# SCCB1508-00.net
KiCad netlist of a schematic drawn in EAGLE
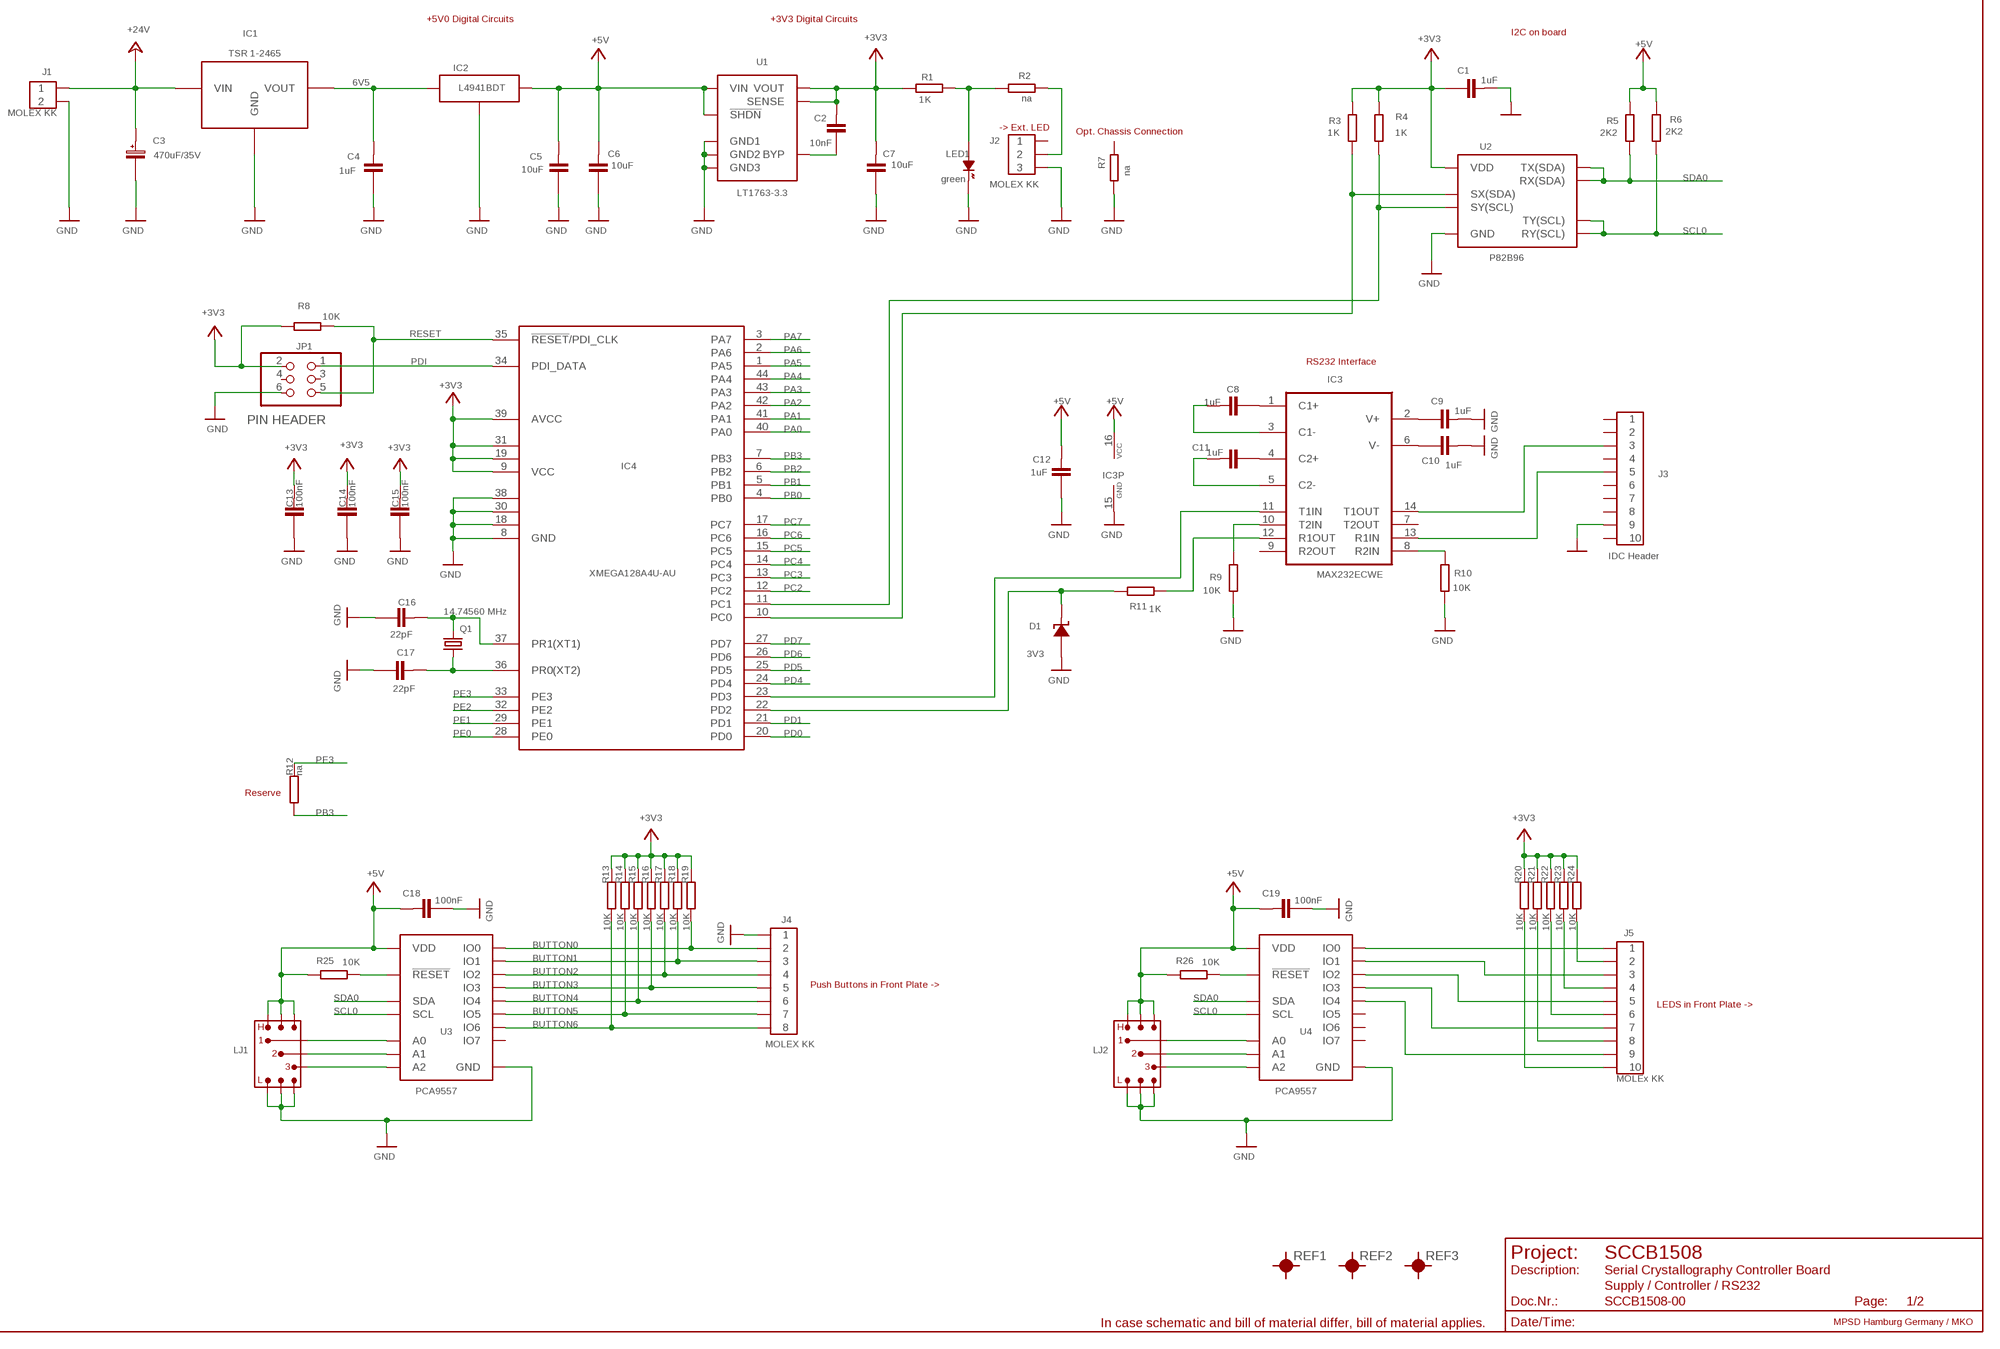
[diagram p0: schematic, sheet 1]
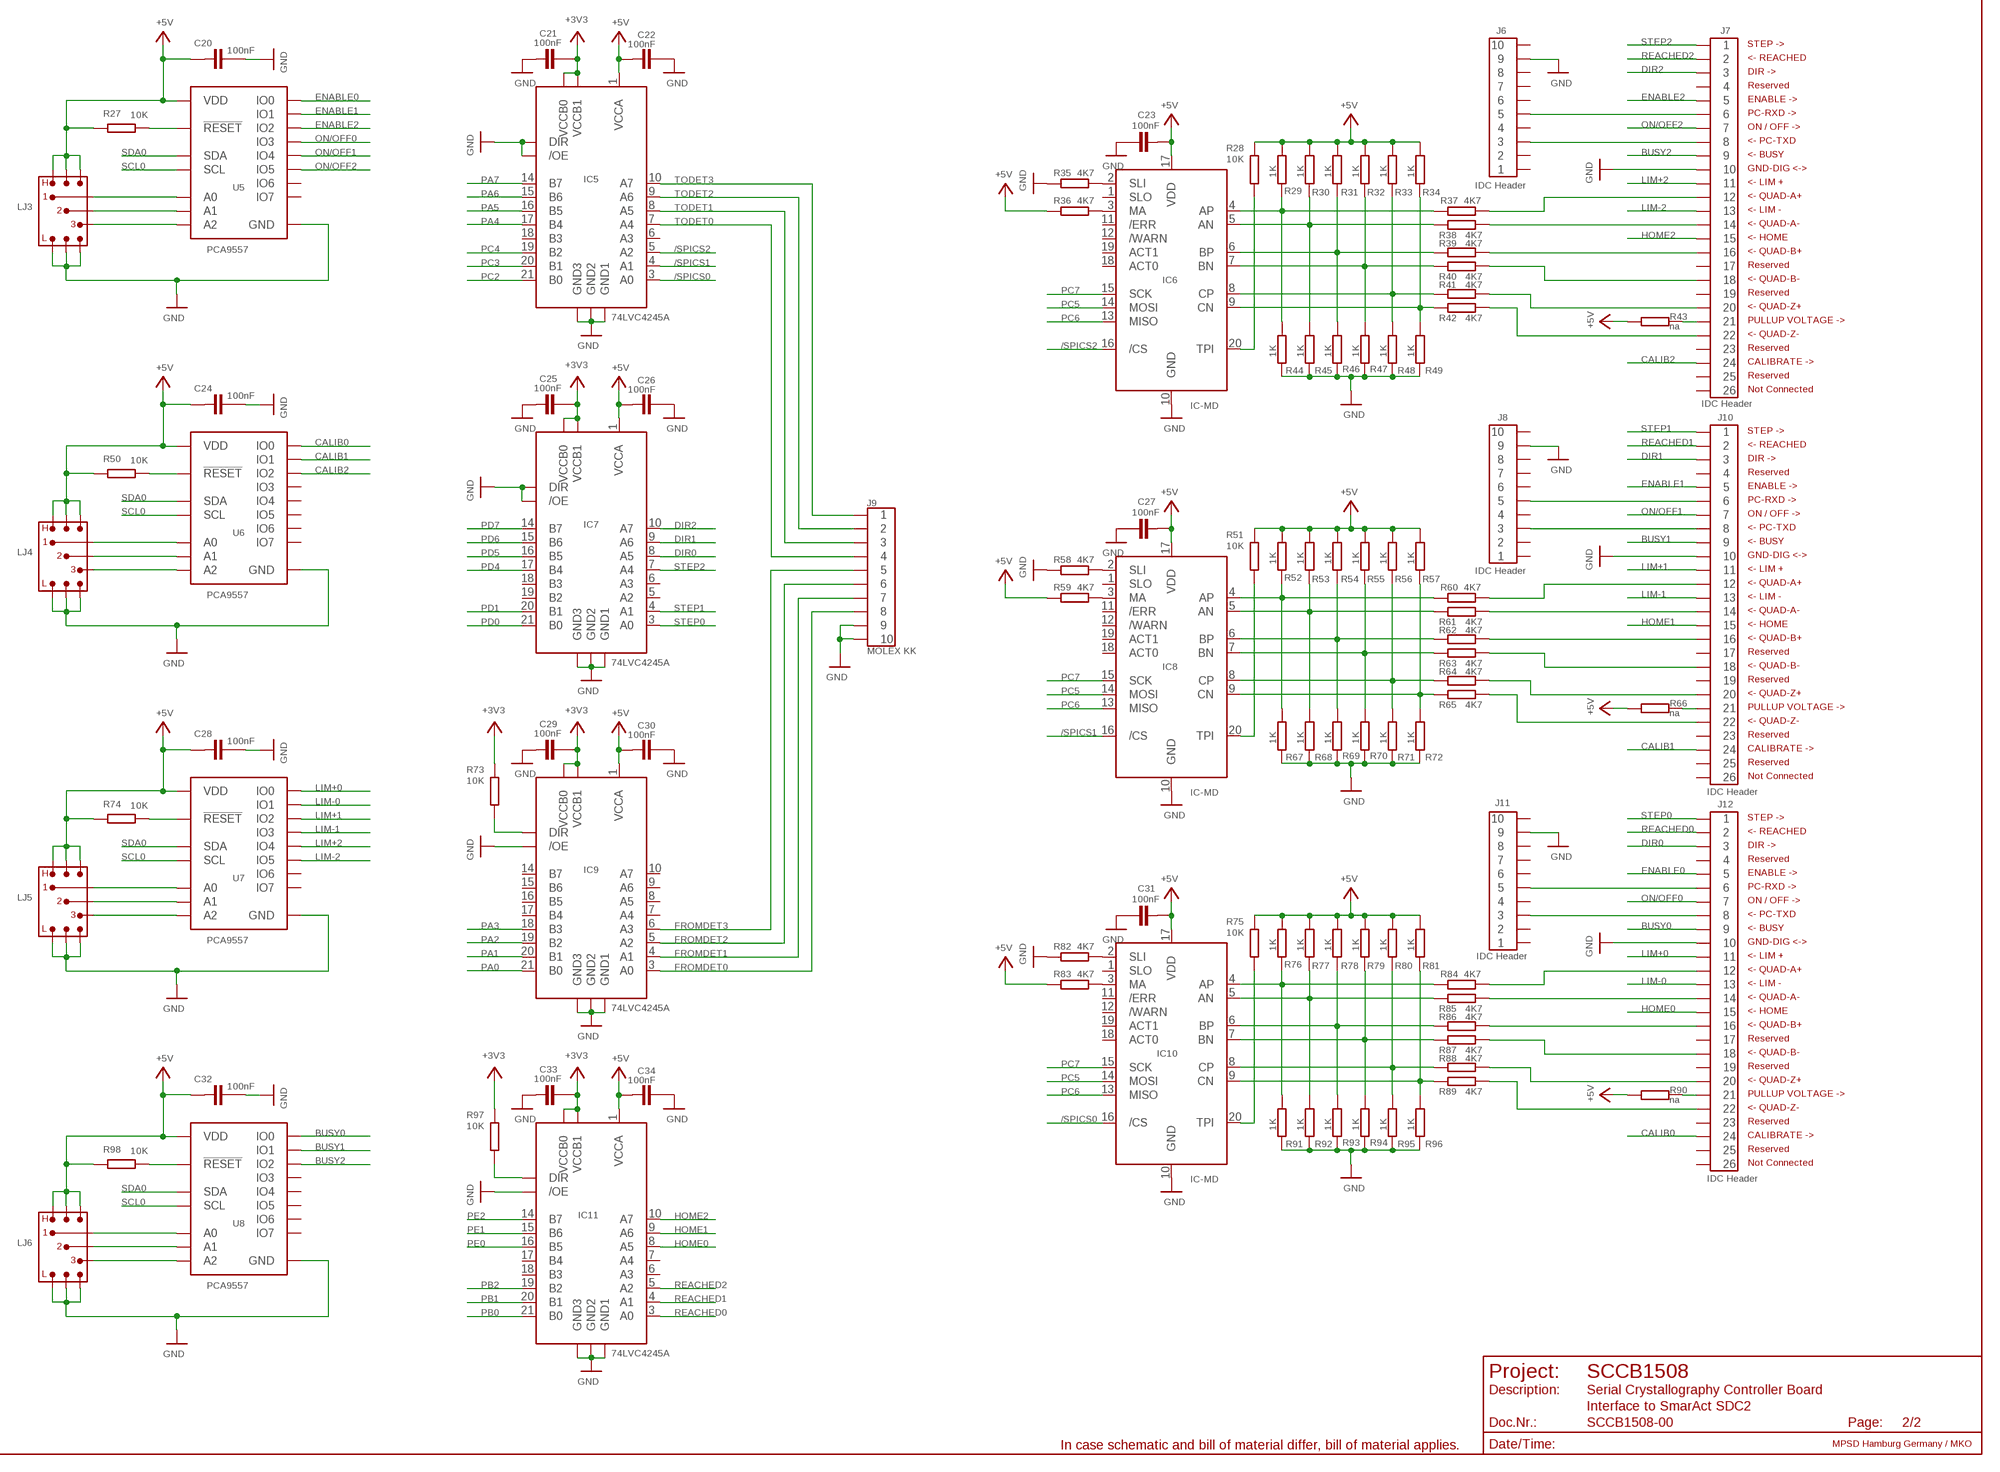
[diagram p1: schematic, sheet 2]

(export (version "E")
  (design (tool "Eeschema 10.0.6"))
  (components
    (comp (ref "C1")
      (value "1uF")
      (footprint "eagle-import:0805")
      (libsource (lib "eagle-import") (part "C_0805"))
    )
    (comp (ref "C2")
      (value "10nF")
      (footprint "eagle-import:0603")
      (libsource (lib "eagle-import") (part "C_0603"))
    )
    (comp (ref "C3")
      (value "470uF/35V")
      (footprint "eagle-import:C_POL_RM5_D16")
      (libsource (lib "eagle-import") (part "C_POL_RM5_D16"))
    )
    (comp (ref "C4")
      (value "1uF")
      (footprint "eagle-import:0805")
      (libsource (lib "eagle-import") (part "C_0805"))
    )
    (comp (ref "C5")
      (value "10uF")
      (footprint "eagle-import:1206")
      (libsource (lib "eagle-import") (part "C_1206"))
    )
    (comp (ref "C6")
      (value "10uF")
      (footprint "eagle-import:1206")
      (libsource (lib "eagle-import") (part "C_1206"))
    )
    (comp (ref "C7")
      (value "10uF")
      (footprint "eagle-import:1206")
      (libsource (lib "eagle-import") (part "C_1206"))
    )
    (comp (ref "C8")
      (value "1uF")
      (footprint "eagle-import:0805")
      (libsource (lib "eagle-import") (part "C_0805"))
    )
    (comp (ref "C9")
      (value "1uF")
      (footprint "eagle-import:0805")
      (libsource (lib "eagle-import") (part "C_0805"))
    )
    (comp (ref "C10")
      (value "1uF")
      (footprint "eagle-import:0805")
      (libsource (lib "eagle-import") (part "C_0805"))
    )
    (comp (ref "C11")
      (value "1uF")
      (footprint "eagle-import:0805")
      (libsource (lib "eagle-import") (part "C_0805"))
    )
    (comp (ref "C12")
      (value "1uF")
      (footprint "eagle-import:0805")
      (libsource (lib "eagle-import") (part "C_0805"))
    )
    (comp (ref "C13")
      (value "100nF")
      (footprint "eagle-import:0603")
      (libsource (lib "eagle-import") (part "C_0603"))
    )
    (comp (ref "C14")
      (value "100nF")
      (footprint "eagle-import:0603")
      (libsource (lib "eagle-import") (part "C_0603"))
    )
    (comp (ref "C15")
      (value "100nF")
      (footprint "eagle-import:0603")
      (libsource (lib "eagle-import") (part "C_0603"))
    )
    (comp (ref "C16")
      (value "22pF")
      (footprint "eagle-import:0603")
      (libsource (lib "eagle-import") (part "C_0603"))
    )
    (comp (ref "C17")
      (value "22pF")
      (footprint "eagle-import:0603")
      (libsource (lib "eagle-import") (part "C_0603"))
    )
    (comp (ref "C18")
      (value "100nF")
      (footprint "eagle-import:0603")
      (libsource (lib "eagle-import") (part "C_0603"))
    )
    (comp (ref "C19")
      (value "100nF")
      (footprint "eagle-import:0603")
      (libsource (lib "eagle-import") (part "C_0603"))
    )
    (comp (ref "D1")
      (value "3V3")
      (footprint "eagle-import:SOT_23")
      (libsource (lib "eagle-import") (part "D_ZENER_SOT23"))
    )
    (comp (ref "IC1")
      (value "TSR 1-2465")
      (footprint "eagle-import:TRACO_TSR_1")
      (libsource (lib "eagle-import") (part "TRACO_TSR_1"))
    )
    (comp (ref "IC2")
      (value "L4941BDT")
      (footprint "eagle-import:D_PAK")
      (libsource (lib "eagle-import") (part "VOLTREG_LIN_3POL_D-PAK"))
    )
    (comp (ref "IC3")
      (value "MAX232ECWE")
      (footprint "eagle-import:SO16L")
      (fields (field (name "MF") "MAXIM") (field (name "MPN") "MAX232ECWE+"))
      (libsource (lib "eagle-import") (part "MAX232ECWE"))
    )
    (comp (ref "IC4")
      (value "XMEGA128A4U-AU")
      (footprint "eagle-import:TQFP44")
      (libsource (lib "eagle-import") (part "XMEGA16A4A"))
    )
    (comp (ref "J1")
      (value "MOLEX KK")
      (footprint "eagle-import:MOLEX_KK_02POL")
      (libsource (lib "eagle-import") (part "CON_02_MOLEX_KK"))
    )
    (comp (ref "J2")
      (value "MOLEX KK")
      (footprint "eagle-import:MOLEX_KK_03POL")
      (libsource (lib "eagle-import") (part "CON_03_MOLEX_KK"))
    )
    (comp (ref "J3")
      (value "IDC Header")
      (footprint "eagle-import:IDC_WANNE_10POL")
      (libsource (lib "eagle-import") (part "CON_10_IDC_10"))
    )
    (comp (ref "J4")
      (value "MOLEX KK")
      (footprint "eagle-import:MOLEX_KK_08POL")
      (libsource (lib "eagle-import") (part "CON_08_MOLEX_KK"))
    )
    (comp (ref "J5")
      (value "MOLEx KK")
      (footprint "eagle-import:MOLEX_KK_10POL")
      (libsource (lib "eagle-import") (part "CON_10_MOLEX-KK"))
    )
    (comp (ref "JP1")
      (value "PIN HEADER")
      (footprint "eagle-import:2X03")
      (libsource (lib "eagle-import") (part "PINHD-2X3"))
    )
    (comp (ref "LED1")
      (value "green")
      (footprint "eagle-import:0603_POL")
      (libsource (lib "eagle-import") (part "D_LED_0603"))
    )
    (comp (ref "LJ1")
      (value "LOETJUMPER_3KHL_")
      (footprint "eagle-import:LOETJUMPER_3KHL")
      (libsource (lib "eagle-import") (part "LOETJUMPER_3KHL_"))
    )
    (comp (ref "LJ2")
      (value "LOETJUMPER_3KHL_")
      (footprint "eagle-import:LOETJUMPER_3KHL")
      (libsource (lib "eagle-import") (part "LOETJUMPER_3KHL_"))
    )
    (comp (ref "Q1")
      (value "14.74560 MHz")
      (footprint "eagle-import:HC49UP")
      (libsource (lib "eagle-import") (part "CRYSTALHC49UP"))
    )
    (comp (ref "R1")
      (value "1K")
      (footprint "eagle-import:0603")
      (libsource (lib "eagle-import") (part "R_0603"))
    )
    (comp (ref "R2")
      (value "na")
      (footprint "eagle-import:1206")
      (libsource (lib "eagle-import") (part "R_1206"))
    )
    (comp (ref "R3")
      (value "1K")
      (footprint "eagle-import:0603")
      (libsource (lib "eagle-import") (part "R_0603"))
    )
    (comp (ref "R4")
      (value "1K")
      (footprint "eagle-import:0603")
      (libsource (lib "eagle-import") (part "R_0603"))
    )
    (comp (ref "R5")
      (value "2K2")
      (footprint "eagle-import:0603")
      (libsource (lib "eagle-import") (part "R_0603"))
    )
    (comp (ref "R6")
      (value "2K2")
      (footprint "eagle-import:0603")
      (libsource (lib "eagle-import") (part "R_0603"))
    )
    (comp (ref "R7")
      (value "na")
      (footprint "eagle-import:0603")
      (libsource (lib "eagle-import") (part "R_0603"))
    )
    (comp (ref "R8")
      (value "10K")
      (footprint "eagle-import:0603")
      (libsource (lib "eagle-import") (part "R_0603"))
    )
    (comp (ref "R9")
      (value "10K")
      (footprint "eagle-import:0603")
      (libsource (lib "eagle-import") (part "R_0603"))
    )
    (comp (ref "R10")
      (value "10K")
      (footprint "eagle-import:0603")
      (libsource (lib "eagle-import") (part "R_0603"))
    )
    (comp (ref "R11")
      (value "1K")
      (footprint "eagle-import:0603")
      (libsource (lib "eagle-import") (part "R_0603"))
    )
    (comp (ref "R12")
      (value "na")
      (footprint "eagle-import:0805")
      (libsource (lib "eagle-import") (part "R_0805"))
    )
    (comp (ref "R13")
      (value "10K")
      (footprint "eagle-import:0603")
      (libsource (lib "eagle-import") (part "R_0603"))
    )
    (comp (ref "R14")
      (value "10K")
      (footprint "eagle-import:0603")
      (libsource (lib "eagle-import") (part "R_0603"))
    )
    (comp (ref "R15")
      (value "10K")
      (footprint "eagle-import:0603")
      (libsource (lib "eagle-import") (part "R_0603"))
    )
    (comp (ref "R16")
      (value "10K")
      (footprint "eagle-import:0603")
      (libsource (lib "eagle-import") (part "R_0603"))
    )
    (comp (ref "R17")
      (value "10K")
      (footprint "eagle-import:0603")
      (libsource (lib "eagle-import") (part "R_0603"))
    )
    (comp (ref "R18")
      (value "10K")
      (footprint "eagle-import:0603")
      (libsource (lib "eagle-import") (part "R_0603"))
    )
    (comp (ref "R19")
      (value "10K")
      (footprint "eagle-import:0603")
      (libsource (lib "eagle-import") (part "R_0603"))
    )
    (comp (ref "R20")
      (value "10K")
      (footprint "eagle-import:0603")
      (libsource (lib "eagle-import") (part "R_0603"))
    )
    (comp (ref "R21")
      (value "10K")
      (footprint "eagle-import:0603")
      (libsource (lib "eagle-import") (part "R_0603"))
    )
    (comp (ref "R22")
      (value "10K")
      (footprint "eagle-import:0603")
      (libsource (lib "eagle-import") (part "R_0603"))
    )
    (comp (ref "R23")
      (value "10K")
      (footprint "eagle-import:0603")
      (libsource (lib "eagle-import") (part "R_0603"))
    )
    (comp (ref "R24")
      (value "10K")
      (footprint "eagle-import:0603")
      (libsource (lib "eagle-import") (part "R_0603"))
    )
    (comp (ref "R25")
      (value "10K")
      (footprint "eagle-import:0603")
      (libsource (lib "eagle-import") (part "R_0603"))
    )
    (comp (ref "R26")
      (value "10K")
      (footprint "eagle-import:0603")
      (libsource (lib "eagle-import") (part "R_0603"))
    )
    (comp (ref "REF1")
      (value "PASSERMARKE_1.0")
      (footprint "eagle-import:PASSERMARKE_01")
      (libsource (lib "eagle-import") (part "PASSERMARKE_1.0"))
    )
    (comp (ref "REF2")
      (value "PASSERMARKE_1.0")
      (footprint "eagle-import:PASSERMARKE_01")
      (libsource (lib "eagle-import") (part "PASSERMARKE_1.0"))
    )
    (comp (ref "REF3")
      (value "PASSERMARKE_1.0")
      (footprint "eagle-import:PASSERMARKE_01")
      (libsource (lib "eagle-import") (part "PASSERMARKE_1.0"))
    )
    (comp (ref "U1")
      (value "LT1763-3.3")
      (footprint "eagle-import:SOIC127P-6-8POL")
      (libsource (lib "eagle-import") (part "LT1763_SO8_ZE"))
    )
    (comp (ref "U2")
      (value "P82B96")
      (footprint "eagle-import:SO_8_BW3.9MM")
      (libsource (lib "eagle-import") (part "P82B96_SO8"))
    )
    (comp (ref "U3")
      (value "PCA9557")
      (footprint "eagle-import:SO_16_BW3.9MM")
      (libsource (lib "eagle-import") (part "PCA9557_SO_16"))
    )
    (comp (ref "U4")
      (value "PCA9557")
      (footprint "eagle-import:SO_16_BW3.9MM")
      (libsource (lib "eagle-import") (part "PCA9557_SO_16"))
    )
    (comp (ref "C20")
      (value "100nF")
      (footprint "eagle-import:0603")
      (libsource (lib "eagle-import") (part "C_0603"))
    )
    (comp (ref "C21")
      (value "100nF")
      (footprint "eagle-import:0603")
      (libsource (lib "eagle-import") (part "C_0603"))
    )
    (comp (ref "C22")
      (value "100nF")
      (footprint "eagle-import:0603")
      (libsource (lib "eagle-import") (part "C_0603"))
    )
    (comp (ref "C23")
      (value "100nF")
      (footprint "eagle-import:0603")
      (libsource (lib "eagle-import") (part "C_0603"))
    )
    (comp (ref "C24")
      (value "100nF")
      (footprint "eagle-import:0603")
      (libsource (lib "eagle-import") (part "C_0603"))
    )
    (comp (ref "C25")
      (value "100nF")
      (footprint "eagle-import:0603")
      (libsource (lib "eagle-import") (part "C_0603"))
    )
    (comp (ref "C26")
      (value "100nF")
      (footprint "eagle-import:0603")
      (libsource (lib "eagle-import") (part "C_0603"))
    )
    (comp (ref "C27")
      (value "100nF")
      (footprint "eagle-import:0603")
      (libsource (lib "eagle-import") (part "C_0603"))
    )
    (comp (ref "C28")
      (value "100nF")
      (footprint "eagle-import:0603")
      (libsource (lib "eagle-import") (part "C_0603"))
    )
    (comp (ref "C29")
      (value "100nF")
      (footprint "eagle-import:0603")
      (libsource (lib "eagle-import") (part "C_0603"))
    )
    (comp (ref "C30")
      (value "100nF")
      (footprint "eagle-import:0603")
      (libsource (lib "eagle-import") (part "C_0603"))
    )
    (comp (ref "C31")
      (value "100nF")
      (footprint "eagle-import:0603")
      (libsource (lib "eagle-import") (part "C_0603"))
    )
    (comp (ref "C32")
      (value "100nF")
      (footprint "eagle-import:0603")
      (libsource (lib "eagle-import") (part "C_0603"))
    )
    (comp (ref "C33")
      (value "100nF")
      (footprint "eagle-import:0603")
      (libsource (lib "eagle-import") (part "C_0603"))
    )
    (comp (ref "C34")
      (value "100nF")
      (footprint "eagle-import:0603")
      (libsource (lib "eagle-import") (part "C_0603"))
    )
    (comp (ref "IC5")
      (value "74LVC4245A")
      (footprint "eagle-import:SO_24_BW5.3MM")
      (libsource (lib "eagle-import") (part "74LVC4245A_SSOP24"))
    )
    (comp (ref "IC6")
      (value "IC-MD")
      (footprint "eagle-import:SSOP_20_BW4.4")
      (libsource (lib "eagle-import") (part "IC-MD_SSOP-20"))
    )
    (comp (ref "IC7")
      (value "74LVC4245A")
      (footprint "eagle-import:SO_24_BW5.3MM")
      (libsource (lib "eagle-import") (part "74LVC4245A_SSOP24"))
    )
    (comp (ref "IC8")
      (value "IC-MD")
      (footprint "eagle-import:SSOP_20_BW4.4")
      (libsource (lib "eagle-import") (part "IC-MD_SSOP-20"))
    )
    (comp (ref "IC9")
      (value "74LVC4245A")
      (footprint "eagle-import:SO_24_BW5.3MM")
      (libsource (lib "eagle-import") (part "74LVC4245A_SSOP24"))
    )
    (comp (ref "IC10")
      (value "IC-MD")
      (footprint "eagle-import:SSOP_20_BW4.4")
      (libsource (lib "eagle-import") (part "IC-MD_SSOP-20"))
    )
    (comp (ref "IC11")
      (value "74LVC4245A")
      (footprint "eagle-import:SO_24_BW5.3MM")
      (libsource (lib "eagle-import") (part "74LVC4245A_SSOP24"))
    )
    (comp (ref "J6")
      (value "IDC Header")
      (footprint "eagle-import:IDC_WANNE_10POL")
      (libsource (lib "eagle-import") (part "CON_10_IDC_10"))
    )
    (comp (ref "J7")
      (value "IDC Header")
      (footprint "eagle-import:IDC_WANNE_26POL")
      (libsource (lib "eagle-import") (part "CON_26_IDC_HEADER"))
    )
    (comp (ref "J8")
      (value "IDC Header")
      (footprint "eagle-import:IDC_WANNE_10POL")
      (libsource (lib "eagle-import") (part "CON_10_IDC_10"))
    )
    (comp (ref "J9")
      (value "MOLEX KK")
      (footprint "eagle-import:MOLEX_KK_10POL")
      (libsource (lib "eagle-import") (part "CON_10_MOLEX-KK"))
    )
    (comp (ref "J10")
      (value "IDC Header")
      (footprint "eagle-import:IDC_WANNE_26POL")
      (libsource (lib "eagle-import") (part "CON_26_IDC_HEADER"))
    )
    (comp (ref "J11")
      (value "IDC Header")
      (footprint "eagle-import:IDC_WANNE_10POL")
      (libsource (lib "eagle-import") (part "CON_10_IDC_10"))
    )
    (comp (ref "J12")
      (value "IDC Header")
      (footprint "eagle-import:IDC_WANNE_26POL")
      (libsource (lib "eagle-import") (part "CON_26_IDC_HEADER"))
    )
    (comp (ref "LJ3")
      (value "LOETJUMPER_3KHL_")
      (footprint "eagle-import:LOETJUMPER_3KHL")
      (libsource (lib "eagle-import") (part "LOETJUMPER_3KHL_"))
    )
    (comp (ref "LJ4")
      (value "LOETJUMPER_3KHL_")
      (footprint "eagle-import:LOETJUMPER_3KHL")
      (libsource (lib "eagle-import") (part "LOETJUMPER_3KHL_"))
    )
    (comp (ref "LJ5")
      (value "LOETJUMPER_3KHL_")
      (footprint "eagle-import:LOETJUMPER_3KHL")
      (libsource (lib "eagle-import") (part "LOETJUMPER_3KHL_"))
    )
    (comp (ref "LJ6")
      (value "LOETJUMPER_3KHL_")
      (footprint "eagle-import:LOETJUMPER_3KHL")
      (libsource (lib "eagle-import") (part "LOETJUMPER_3KHL_"))
    )
    (comp (ref "R27")
      (value "10K")
      (footprint "eagle-import:0603")
      (libsource (lib "eagle-import") (part "R_0603"))
    )
    (comp (ref "R28")
      (value "10K")
      (footprint "eagle-import:0603")
      (libsource (lib "eagle-import") (part "R_0603"))
    )
    (comp (ref "R29")
      (value "1K")
      (footprint "eagle-import:0603")
      (libsource (lib "eagle-import") (part "R_0603"))
    )
    (comp (ref "R30")
      (value "1K")
      (footprint "eagle-import:0603")
      (libsource (lib "eagle-import") (part "R_0603"))
    )
    (comp (ref "R31")
      (value "1K")
      (footprint "eagle-import:0603")
      (libsource (lib "eagle-import") (part "R_0603"))
    )
    (comp (ref "R32")
      (value "1K")
      (footprint "eagle-import:0603")
      (libsource (lib "eagle-import") (part "R_0603"))
    )
    (comp (ref "R33")
      (value "1K")
      (footprint "eagle-import:0603")
      (libsource (lib "eagle-import") (part "R_0603"))
    )
    (comp (ref "R34")
      (value "1K")
      (footprint "eagle-import:0603")
      (libsource (lib "eagle-import") (part "R_0603"))
    )
    (comp (ref "R35")
      (value "4K7")
      (footprint "eagle-import:0603")
      (libsource (lib "eagle-import") (part "R_0603"))
    )
    (comp (ref "R36")
      (value "4K7")
      (footprint "eagle-import:0603")
      (libsource (lib "eagle-import") (part "R_0603"))
    )
    (comp (ref "R37")
      (value "4K7")
      (footprint "eagle-import:0603")
      (libsource (lib "eagle-import") (part "R_0603"))
    )
    (comp (ref "R38")
      (value "4K7")
      (footprint "eagle-import:0603")
      (libsource (lib "eagle-import") (part "R_0603"))
    )
    (comp (ref "R39")
      (value "4K7")
      (footprint "eagle-import:0603")
      (libsource (lib "eagle-import") (part "R_0603"))
    )
    (comp (ref "R40")
      (value "4K7")
      (footprint "eagle-import:0603")
      (libsource (lib "eagle-import") (part "R_0603"))
    )
    (comp (ref "R41")
      (value "4K7")
      (footprint "eagle-import:0603")
      (libsource (lib "eagle-import") (part "R_0603"))
    )
    (comp (ref "R42")
      (value "4K7")
      (footprint "eagle-import:0603")
      (libsource (lib "eagle-import") (part "R_0603"))
    )
    (comp (ref "R43")
      (value "na")
      (footprint "eagle-import:RM10L10B2.5")
      (libsource (lib "eagle-import") (part "R_RM10B2.5"))
    )
    (comp (ref "R44")
      (value "1K")
      (footprint "eagle-import:0603")
      (libsource (lib "eagle-import") (part "R_0603"))
    )
    (comp (ref "R45")
      (value "1K")
      (footprint "eagle-import:0603")
      (libsource (lib "eagle-import") (part "R_0603"))
    )
    (comp (ref "R46")
      (value "1K")
      (footprint "eagle-import:0603")
      (libsource (lib "eagle-import") (part "R_0603"))
    )
    (comp (ref "R47")
      (value "1K")
      (footprint "eagle-import:0603")
      (libsource (lib "eagle-import") (part "R_0603"))
    )
    (comp (ref "R48")
      (value "1K")
      (footprint "eagle-import:0603")
      (libsource (lib "eagle-import") (part "R_0603"))
    )
    (comp (ref "R49")
      (value "1K")
      (footprint "eagle-import:0603")
      (libsource (lib "eagle-import") (part "R_0603"))
    )
    (comp (ref "R50")
      (value "10K")
      (footprint "eagle-import:0603")
      (libsource (lib "eagle-import") (part "R_0603"))
    )
    (comp (ref "R51")
      (value "10K")
      (footprint "eagle-import:0603")
      (libsource (lib "eagle-import") (part "R_0603"))
    )
    (comp (ref "R52")
      (value "1K")
      (footprint "eagle-import:0603")
      (libsource (lib "eagle-import") (part "R_0603"))
    )
    (comp (ref "R53")
      (value "1K")
      (footprint "eagle-import:0603")
      (libsource (lib "eagle-import") (part "R_0603"))
    )
    (comp (ref "R54")
      (value "1K")
      (footprint "eagle-import:0603")
      (libsource (lib "eagle-import") (part "R_0603"))
    )
    (comp (ref "R55")
      (value "1K")
      (footprint "eagle-import:0603")
      (libsource (lib "eagle-import") (part "R_0603"))
    )
    (comp (ref "R56")
      (value "1K")
      (footprint "eagle-import:0603")
      (libsource (lib "eagle-import") (part "R_0603"))
    )
    (comp (ref "R57")
      (value "1K")
      (footprint "eagle-import:0603")
      (libsource (lib "eagle-import") (part "R_0603"))
    )
    (comp (ref "R58")
      (value "4K7")
      (footprint "eagle-import:0603")
      (libsource (lib "eagle-import") (part "R_0603"))
    )
    (comp (ref "R59")
      (value "4K7")
      (footprint "eagle-import:0603")
      (libsource (lib "eagle-import") (part "R_0603"))
    )
    (comp (ref "R60")
      (value "4K7")
      (footprint "eagle-import:0603")
      (libsource (lib "eagle-import") (part "R_0603"))
    )
    (comp (ref "R61")
      (value "4K7")
      (footprint "eagle-import:0603")
      (libsource (lib "eagle-import") (part "R_0603"))
    )
    (comp (ref "R62")
      (value "4K7")
      (footprint "eagle-import:0603")
      (libsource (lib "eagle-import") (part "R_0603"))
    )
    (comp (ref "R63")
      (value "4K7")
      (footprint "eagle-import:0603")
      (libsource (lib "eagle-import") (part "R_0603"))
    )
    (comp (ref "R64")
      (value "4K7")
      (footprint "eagle-import:0603")
      (libsource (lib "eagle-import") (part "R_0603"))
    )
    (comp (ref "R65")
      (value "4K7")
      (footprint "eagle-import:0603")
      (libsource (lib "eagle-import") (part "R_0603"))
    )
    (comp (ref "R66")
      (value "na")
      (footprint "eagle-import:RM10L10B2.5")
      (libsource (lib "eagle-import") (part "R_RM10B2.5"))
    )
    (comp (ref "R67")
      (value "1K")
      (footprint "eagle-import:0603")
      (libsource (lib "eagle-import") (part "R_0603"))
    )
    (comp (ref "R68")
      (value "1K")
      (footprint "eagle-import:0603")
      (libsource (lib "eagle-import") (part "R_0603"))
    )
    (comp (ref "R69")
      (value "1K")
      (footprint "eagle-import:0603")
      (libsource (lib "eagle-import") (part "R_0603"))
    )
    (comp (ref "R70")
      (value "1K")
      (footprint "eagle-import:0603")
      (libsource (lib "eagle-import") (part "R_0603"))
    )
    (comp (ref "R71")
      (value "1K")
      (footprint "eagle-import:0603")
      (libsource (lib "eagle-import") (part "R_0603"))
    )
    (comp (ref "R72")
      (value "1K")
      (footprint "eagle-import:0603")
      (libsource (lib "eagle-import") (part "R_0603"))
    )
    (comp (ref "R73")
      (value "10K")
      (footprint "eagle-import:0603")
      (libsource (lib "eagle-import") (part "R_0603"))
    )
    (comp (ref "R74")
      (value "10K")
      (footprint "eagle-import:0603")
      (libsource (lib "eagle-import") (part "R_0603"))
    )
    (comp (ref "R75")
      (value "10K")
      (footprint "eagle-import:0603")
      (libsource (lib "eagle-import") (part "R_0603"))
    )
    (comp (ref "R76")
      (value "1K")
      (footprint "eagle-import:0603")
      (libsource (lib "eagle-import") (part "R_0603"))
    )
    (comp (ref "R77")
      (value "1K")
      (footprint "eagle-import:0603")
      (libsource (lib "eagle-import") (part "R_0603"))
    )
    (comp (ref "R78")
      (value "1K")
      (footprint "eagle-import:0603")
      (libsource (lib "eagle-import") (part "R_0603"))
    )
    (comp (ref "R79")
      (value "1K")
      (footprint "eagle-import:0603")
      (libsource (lib "eagle-import") (part "R_0603"))
    )
    (comp (ref "R80")
      (value "1K")
      (footprint "eagle-import:0603")
      (libsource (lib "eagle-import") (part "R_0603"))
    )
    (comp (ref "R81")
      (value "1K")
      (footprint "eagle-import:0603")
      (libsource (lib "eagle-import") (part "R_0603"))
    )
    (comp (ref "R82")
      (value "4K7")
      (footprint "eagle-import:0603")
      (libsource (lib "eagle-import") (part "R_0603"))
    )
    (comp (ref "R83")
      (value "4K7")
      (footprint "eagle-import:0603")
      (libsource (lib "eagle-import") (part "R_0603"))
    )
    (comp (ref "R84")
      (value "4K7")
      (footprint "eagle-import:0603")
      (libsource (lib "eagle-import") (part "R_0603"))
    )
    (comp (ref "R85")
      (value "4K7")
      (footprint "eagle-import:0603")
      (libsource (lib "eagle-import") (part "R_0603"))
    )
    (comp (ref "R86")
      (value "4K7")
      (footprint "eagle-import:0603")
      (libsource (lib "eagle-import") (part "R_0603"))
    )
    (comp (ref "R87")
      (value "4K7")
      (footprint "eagle-import:0603")
      (libsource (lib "eagle-import") (part "R_0603"))
    )
    (comp (ref "R88")
      (value "4K7")
      (footprint "eagle-import:0603")
      (libsource (lib "eagle-import") (part "R_0603"))
    )
    (comp (ref "R89")
      (value "4K7")
      (footprint "eagle-import:0603")
      (libsource (lib "eagle-import") (part "R_0603"))
    )
    (comp (ref "R90")
      (value "na")
      (footprint "eagle-import:RM10L10B2.5")
      (libsource (lib "eagle-import") (part "R_RM10B2.5"))
    )
    (comp (ref "R91")
      (value "1K")
      (footprint "eagle-import:0603")
      (libsource (lib "eagle-import") (part "R_0603"))
    )
    (comp (ref "R92")
      (value "1K")
      (footprint "eagle-import:0603")
      (libsource (lib "eagle-import") (part "R_0603"))
    )
    (comp (ref "R93")
      (value "1K")
      (footprint "eagle-import:0603")
      (libsource (lib "eagle-import") (part "R_0603"))
    )
    (comp (ref "R94")
      (value "1K")
      (footprint "eagle-import:0603")
      (libsource (lib "eagle-import") (part "R_0603"))
    )
    (comp (ref "R95")
      (value "1K")
      (footprint "eagle-import:0603")
      (libsource (lib "eagle-import") (part "R_0603"))
    )
    (comp (ref "R96")
      (value "1K")
      (footprint "eagle-import:0603")
      (libsource (lib "eagle-import") (part "R_0603"))
    )
    (comp (ref "R97")
      (value "10K")
      (footprint "eagle-import:0603")
      (libsource (lib "eagle-import") (part "R_0603"))
    )
    (comp (ref "R98")
      (value "10K")
      (footprint "eagle-import:0603")
      (libsource (lib "eagle-import") (part "R_0603"))
    )
    (comp (ref "U5")
      (value "PCA9557")
      (footprint "eagle-import:SO_16_BW3.9MM")
      (libsource (lib "eagle-import") (part "PCA9557_SO_16"))
    )
    (comp (ref "U6")
      (value "PCA9557")
      (footprint "eagle-import:SO_16_BW3.9MM")
      (libsource (lib "eagle-import") (part "PCA9557_SO_16"))
    )
    (comp (ref "U7")
      (value "PCA9557")
      (footprint "eagle-import:SO_16_BW3.9MM")
      (libsource (lib "eagle-import") (part "PCA9557_SO_16"))
    )
    (comp (ref "U8")
      (value "PCA9557")
      (footprint "eagle-import:SO_16_BW3.9MM")
      (libsource (lib "eagle-import") (part "PCA9557_SO_16"))
    )
  )
  (nets
    (net (code "1") (name "+3V3") (class "Default")
      (node (ref "C1") (pin "1") (pinfunction "P$1_1") (pintype "bidirectional"))
      (node (ref "C13") (pin "2") (pinfunction "P$2_2") (pintype "bidirectional"))
      (node (ref "C14") (pin "2") (pinfunction "P$2_2") (pintype "bidirectional"))
      (node (ref "C15") (pin "2") (pinfunction "P$2_2") (pintype "bidirectional"))
      (node (ref "C2") (pin "2") (pinfunction "P$2_2") (pintype "bidirectional"))
      (node (ref "C21") (pin "1") (pinfunction "P$1_1") (pintype "bidirectional"))
      (node (ref "C25") (pin "1") (pinfunction "P$1_1") (pintype "bidirectional"))
      (node (ref "C29") (pin "1") (pinfunction "P$1_1") (pintype "bidirectional"))
      (node (ref "C33") (pin "1") (pinfunction "P$1_1") (pintype "bidirectional"))
      (node (ref "C7") (pin "2") (pinfunction "P$2_2") (pintype "bidirectional"))
      (node (ref "IC11") (pin "23") (pinfunction "VCCB0_23") (pintype "bidirectional"))
      (node (ref "IC11") (pin "24") (pinfunction "VCCB1_24") (pintype "bidirectional"))
      (node (ref "IC4") (pin "19") (pinfunction "VCC1_19") (pintype "power_in"))
      (node (ref "IC4") (pin "31") (pinfunction "VCC2_31") (pintype "power_in"))
      (node (ref "IC4") (pin "39") (pinfunction "AVCC_39") (pintype "power_in"))
      (node (ref "IC4") (pin "9") (pinfunction "VCC_9") (pintype "power_in"))
      (node (ref "IC5") (pin "23") (pinfunction "VCCB0_23") (pintype "bidirectional"))
      (node (ref "IC5") (pin "24") (pinfunction "VCCB1_24") (pintype "bidirectional"))
      (node (ref "IC7") (pin "23") (pinfunction "VCCB0_23") (pintype "bidirectional"))
      (node (ref "IC7") (pin "24") (pinfunction "VCCB1_24") (pintype "bidirectional"))
      (node (ref "IC9") (pin "23") (pinfunction "VCCB0_23") (pintype "bidirectional"))
      (node (ref "IC9") (pin "24") (pinfunction "VCCB1_24") (pintype "bidirectional"))
      (node (ref "JP1") (pin "2") (pinfunction "2_2") (pintype "passive"))
      (node (ref "R1") (pin "2") (pinfunction "P$2_2") (pintype "bidirectional"))
      (node (ref "R13") (pin "1") (pinfunction "P$1_1") (pintype "bidirectional"))
      (node (ref "R14") (pin "1") (pinfunction "P$1_1") (pintype "bidirectional"))
      (node (ref "R15") (pin "1") (pinfunction "P$1_1") (pintype "bidirectional"))
      (node (ref "R16") (pin "1") (pinfunction "P$1_1") (pintype "bidirectional"))
      (node (ref "R17") (pin "1") (pinfunction "P$1_1") (pintype "bidirectional"))
      (node (ref "R18") (pin "1") (pinfunction "P$1_1") (pintype "bidirectional"))
      (node (ref "R19") (pin "1") (pinfunction "P$1_1") (pintype "bidirectional"))
      (node (ref "R20") (pin "1") (pinfunction "P$1_1") (pintype "bidirectional"))
      (node (ref "R21") (pin "1") (pinfunction "P$1_1") (pintype "bidirectional"))
      (node (ref "R22") (pin "1") (pinfunction "P$1_1") (pintype "bidirectional"))
      (node (ref "R23") (pin "1") (pinfunction "P$1_1") (pintype "bidirectional"))
      (node (ref "R24") (pin "1") (pinfunction "P$1_1") (pintype "bidirectional"))
      (node (ref "R3") (pin "1") (pinfunction "P$1_1") (pintype "bidirectional"))
      (node (ref "R4") (pin "1") (pinfunction "P$1_1") (pintype "bidirectional"))
      (node (ref "R73") (pin "1") (pinfunction "P$1_1") (pintype "bidirectional"))
      (node (ref "R8") (pin "1") (pinfunction "P$1_1") (pintype "bidirectional"))
      (node (ref "R97") (pin "1") (pinfunction "P$1_1") (pintype "bidirectional"))
      (node (ref "U1") (pin "1") (pinfunction "VOUT_1") (pintype "bidirectional"))
      (node (ref "U1") (pin "2") (pinfunction "SENSE_2") (pintype "bidirectional"))
      (node (ref "U2") (pin "8") (pinfunction "VDD_8") (pintype "bidirectional"))
    )
    (net (code "2") (name "+5V") (class "Default")
      (node (ref "C12") (pin "2") (pinfunction "P$2_2") (pintype "bidirectional"))
      (node (ref "C18") (pin "2") (pinfunction "P$2_2") (pintype "bidirectional"))
      (node (ref "C19") (pin "2") (pinfunction "P$2_2") (pintype "bidirectional"))
      (node (ref "C20") (pin "2") (pinfunction "P$2_2") (pintype "bidirectional"))
      (node (ref "C22") (pin "2") (pinfunction "P$2_2") (pintype "bidirectional"))
      (node (ref "C23") (pin "2") (pinfunction "P$2_2") (pintype "bidirectional"))
      (node (ref "C24") (pin "2") (pinfunction "P$2_2") (pintype "bidirectional"))
      (node (ref "C26") (pin "2") (pinfunction "P$2_2") (pintype "bidirectional"))
      (node (ref "C27") (pin "2") (pinfunction "P$2_2") (pintype "bidirectional"))
      (node (ref "C28") (pin "2") (pinfunction "P$2_2") (pintype "bidirectional"))
      (node (ref "C30") (pin "2") (pinfunction "P$2_2") (pintype "bidirectional"))
      (node (ref "C31") (pin "2") (pinfunction "P$2_2") (pintype "bidirectional"))
      (node (ref "C32") (pin "2") (pinfunction "P$2_2") (pintype "bidirectional"))
      (node (ref "C34") (pin "2") (pinfunction "P$2_2") (pintype "bidirectional"))
      (node (ref "C5") (pin "2") (pinfunction "P$2_2") (pintype "bidirectional"))
      (node (ref "C6") (pin "2") (pinfunction "P$2_2") (pintype "bidirectional"))
      (node (ref "IC10") (pin "17") (pinfunction "VDD_17") (pintype "bidirectional"))
      (node (ref "IC11") (pin "1") (pinfunction "VCCA_1") (pintype "bidirectional"))
      (node (ref "IC2") (pin "3") (pinfunction "OUT_3") (pintype "bidirectional"))
      (node (ref "IC3") (pin "16") (pinfunction "VCC_16") (pintype "power_in"))
      (node (ref "IC5") (pin "1") (pinfunction "VCCA_1") (pintype "bidirectional"))
      (node (ref "IC6") (pin "17") (pinfunction "VDD_17") (pintype "bidirectional"))
      (node (ref "IC7") (pin "1") (pinfunction "VCCA_1") (pintype "bidirectional"))
      (node (ref "IC8") (pin "17") (pinfunction "VDD_17") (pintype "bidirectional"))
      (node (ref "IC9") (pin "1") (pinfunction "VCCA_1") (pintype "bidirectional"))
      (node (ref "LJ1") (pin "H1") (pinfunction "H1_H1") (pintype "bidirectional"))
      (node (ref "LJ1") (pin "H2") (pinfunction "H2_H2") (pintype "bidirectional"))
      (node (ref "LJ1") (pin "H3") (pinfunction "H3_H3") (pintype "bidirectional"))
      (node (ref "LJ2") (pin "H1") (pinfunction "H1_H1") (pintype "bidirectional"))
      (node (ref "LJ2") (pin "H2") (pinfunction "H2_H2") (pintype "bidirectional"))
      (node (ref "LJ2") (pin "H3") (pinfunction "H3_H3") (pintype "bidirectional"))
      (node (ref "LJ3") (pin "H1") (pinfunction "H1_H1") (pintype "bidirectional"))
      (node (ref "LJ3") (pin "H2") (pinfunction "H2_H2") (pintype "bidirectional"))
      (node (ref "LJ3") (pin "H3") (pinfunction "H3_H3") (pintype "bidirectional"))
      (node (ref "LJ4") (pin "H1") (pinfunction "H1_H1") (pintype "bidirectional"))
      (node (ref "LJ4") (pin "H2") (pinfunction "H2_H2") (pintype "bidirectional"))
      (node (ref "LJ4") (pin "H3") (pinfunction "H3_H3") (pintype "bidirectional"))
      (node (ref "LJ5") (pin "H1") (pinfunction "H1_H1") (pintype "bidirectional"))
      (node (ref "LJ5") (pin "H2") (pinfunction "H2_H2") (pintype "bidirectional"))
      (node (ref "LJ5") (pin "H3") (pinfunction "H3_H3") (pintype "bidirectional"))
      (node (ref "LJ6") (pin "H1") (pinfunction "H1_H1") (pintype "bidirectional"))
      (node (ref "LJ6") (pin "H2") (pinfunction "H2_H2") (pintype "bidirectional"))
      (node (ref "LJ6") (pin "H3") (pinfunction "H3_H3") (pintype "bidirectional"))
      (node (ref "R25") (pin "2") (pinfunction "P$2_2") (pintype "bidirectional"))
      (node (ref "R26") (pin "2") (pinfunction "P$2_2") (pintype "bidirectional"))
      (node (ref "R27") (pin "2") (pinfunction "P$2_2") (pintype "bidirectional"))
      (node (ref "R28") (pin "1") (pinfunction "P$1_1") (pintype "bidirectional"))
      (node (ref "R29") (pin "2") (pinfunction "P$2_2") (pintype "bidirectional"))
      (node (ref "R30") (pin "2") (pinfunction "P$2_2") (pintype "bidirectional"))
      (node (ref "R31") (pin "2") (pinfunction "P$2_2") (pintype "bidirectional"))
      (node (ref "R32") (pin "2") (pinfunction "P$2_2") (pintype "bidirectional"))
      (node (ref "R33") (pin "2") (pinfunction "P$2_2") (pintype "bidirectional"))
      (node (ref "R34") (pin "2") (pinfunction "P$2_2") (pintype "bidirectional"))
      (node (ref "R36") (pin "1") (pinfunction "P$1_1") (pintype "bidirectional"))
      (node (ref "R43") (pin "1") (pinfunction "P$1_1") (pintype "bidirectional"))
      (node (ref "R5") (pin "1") (pinfunction "P$1_1") (pintype "bidirectional"))
      (node (ref "R50") (pin "2") (pinfunction "P$2_2") (pintype "bidirectional"))
      (node (ref "R51") (pin "1") (pinfunction "P$1_1") (pintype "bidirectional"))
      (node (ref "R52") (pin "2") (pinfunction "P$2_2") (pintype "bidirectional"))
      (node (ref "R53") (pin "2") (pinfunction "P$2_2") (pintype "bidirectional"))
      (node (ref "R54") (pin "2") (pinfunction "P$2_2") (pintype "bidirectional"))
      (node (ref "R55") (pin "2") (pinfunction "P$2_2") (pintype "bidirectional"))
      (node (ref "R56") (pin "2") (pinfunction "P$2_2") (pintype "bidirectional"))
      (node (ref "R57") (pin "2") (pinfunction "P$2_2") (pintype "bidirectional"))
      (node (ref "R59") (pin "1") (pinfunction "P$1_1") (pintype "bidirectional"))
      (node (ref "R6") (pin "1") (pinfunction "P$1_1") (pintype "bidirectional"))
      (node (ref "R66") (pin "1") (pinfunction "P$1_1") (pintype "bidirectional"))
      (node (ref "R74") (pin "2") (pinfunction "P$2_2") (pintype "bidirectional"))
      (node (ref "R75") (pin "1") (pinfunction "P$1_1") (pintype "bidirectional"))
      (node (ref "R76") (pin "2") (pinfunction "P$2_2") (pintype "bidirectional"))
      (node (ref "R77") (pin "2") (pinfunction "P$2_2") (pintype "bidirectional"))
      (node (ref "R78") (pin "2") (pinfunction "P$2_2") (pintype "bidirectional"))
      (node (ref "R79") (pin "2") (pinfunction "P$2_2") (pintype "bidirectional"))
      (node (ref "R80") (pin "2") (pinfunction "P$2_2") (pintype "bidirectional"))
      (node (ref "R81") (pin "2") (pinfunction "P$2_2") (pintype "bidirectional"))
      (node (ref "R83") (pin "1") (pinfunction "P$1_1") (pintype "bidirectional"))
      (node (ref "R90") (pin "1") (pinfunction "P$1_1") (pintype "bidirectional"))
      (node (ref "R98") (pin "2") (pinfunction "P$2_2") (pintype "bidirectional"))
      (node (ref "U1") (pin "5") (pinfunction "~{SHDN}_5") (pintype "bidirectional"))
      (node (ref "U1") (pin "8") (pinfunction "VIN_8") (pintype "bidirectional"))
      (node (ref "U3") (pin "16") (pinfunction "VDD_16") (pintype "bidirectional"))
      (node (ref "U4") (pin "16") (pinfunction "VDD_16") (pintype "bidirectional"))
      (node (ref "U5") (pin "16") (pinfunction "VDD_16") (pintype "bidirectional"))
      (node (ref "U6") (pin "16") (pinfunction "VDD_16") (pintype "bidirectional"))
      (node (ref "U7") (pin "16") (pinfunction "VDD_16") (pintype "bidirectional"))
      (node (ref "U8") (pin "16") (pinfunction "VDD_16") (pintype "bidirectional"))
    )
    (net (code "3") (name "+24V") (class "Default")
      (node (ref "C3") (pin "1") (pinfunction "PLUS_1") (pintype "bidirectional"))
      (node (ref "IC1") (pin "P$1") (pinfunction "VIN_P$1") (pintype "bidirectional"))
      (node (ref "J1") (pin "P$1") (pinfunction "1_P$1") (pintype "bidirectional"))
    )
    (net (code "4") (name "6V5") (class "Default")
      (node (ref "C4") (pin "2") (pinfunction "P$2_2") (pintype "bidirectional"))
      (node (ref "IC1") (pin "P$3") (pinfunction "VOUT_P$3") (pintype "bidirectional"))
      (node (ref "IC2") (pin "1") (pinfunction "IN_1") (pintype "bidirectional"))
    )
    (net (code "5") (name "BUSY0") (class "Default")
      (node (ref "J12") (pin "9") (pinfunction "9_9") (pintype "bidirectional"))
      (node (ref "U8") (pin "6") (pinfunction "IO0_6") (pintype "bidirectional"))
    )
    (net (code "6") (name "BUSY1") (class "Default")
      (node (ref "J10") (pin "9") (pinfunction "9_9") (pintype "bidirectional"))
      (node (ref "U8") (pin "7") (pinfunction "IO1_7") (pintype "bidirectional"))
    )
    (net (code "7") (name "BUSY2") (class "Default")
      (node (ref "J7") (pin "9") (pinfunction "9_9") (pintype "bidirectional"))
      (node (ref "U8") (pin "9") (pinfunction "IO2_9") (pintype "bidirectional"))
    )
    (net (code "8") (name "BUTTON0") (class "Default")
      (node (ref "J4") (pin "P$2") (pinfunction "2_P$2") (pintype "bidirectional"))
      (node (ref "R19") (pin "2") (pinfunction "P$2_2") (pintype "bidirectional"))
      (node (ref "U3") (pin "6") (pinfunction "IO0_6") (pintype "bidirectional"))
    )
    (net (code "9") (name "BUTTON1") (class "Default")
      (node (ref "J4") (pin "P$3") (pinfunction "3_P$3") (pintype "bidirectional"))
      (node (ref "R18") (pin "2") (pinfunction "P$2_2") (pintype "bidirectional"))
      (node (ref "U3") (pin "7") (pinfunction "IO1_7") (pintype "bidirectional"))
    )
    (net (code "10") (name "BUTTON2") (class "Default")
      (node (ref "J4") (pin "P$4") (pinfunction "4_P$4") (pintype "bidirectional"))
      (node (ref "R17") (pin "2") (pinfunction "P$2_2") (pintype "bidirectional"))
      (node (ref "U3") (pin "9") (pinfunction "IO2_9") (pintype "bidirectional"))
    )
    (net (code "11") (name "BUTTON3") (class "Default")
      (node (ref "J4") (pin "P$5") (pinfunction "5_P$5") (pintype "bidirectional"))
      (node (ref "R16") (pin "2") (pinfunction "P$2_2") (pintype "bidirectional"))
      (node (ref "U3") (pin "10") (pinfunction "IO3_10") (pintype "bidirectional"))
    )
    (net (code "12") (name "BUTTON4") (class "Default")
      (node (ref "J4") (pin "P$6") (pinfunction "6_P$6") (pintype "bidirectional"))
      (node (ref "R15") (pin "2") (pinfunction "P$2_2") (pintype "bidirectional"))
      (node (ref "U3") (pin "11") (pinfunction "IO4_11") (pintype "bidirectional"))
    )
    (net (code "13") (name "BUTTON5") (class "Default")
      (node (ref "J4") (pin "P$7") (pinfunction "7_P$7") (pintype "bidirectional"))
      (node (ref "R14") (pin "2") (pinfunction "P$2_2") (pintype "bidirectional"))
      (node (ref "U3") (pin "12") (pinfunction "IO5_12") (pintype "bidirectional"))
    )
    (net (code "14") (name "BUTTON6") (class "Default")
      (node (ref "J4") (pin "P$8") (pinfunction "8_P$8") (pintype "bidirectional"))
      (node (ref "R13") (pin "2") (pinfunction "P$2_2") (pintype "bidirectional"))
      (node (ref "U3") (pin "13") (pinfunction "IO6_13") (pintype "bidirectional"))
    )
    (net (code "15") (name "CALIB0") (class "Default")
      (node (ref "J12") (pin "24") (pinfunction "24_24") (pintype "bidirectional"))
      (node (ref "U6") (pin "6") (pinfunction "IO0_6") (pintype "bidirectional"))
    )
    (net (code "16") (name "CALIB1") (class "Default")
      (node (ref "J10") (pin "24") (pinfunction "24_24") (pintype "bidirectional"))
      (node (ref "U6") (pin "7") (pinfunction "IO1_7") (pintype "bidirectional"))
    )
    (net (code "17") (name "CALIB2") (class "Default")
      (node (ref "J7") (pin "24") (pinfunction "24_24") (pintype "bidirectional"))
      (node (ref "U6") (pin "9") (pinfunction "IO2_9") (pintype "bidirectional"))
    )
    (net (code "18") (name "DIR0") (class "Default")
      (node (ref "IC7") (pin "8") (pinfunction "A5_8") (pintype "bidirectional"))
      (node (ref "J12") (pin "3") (pinfunction "3_3") (pintype "bidirectional"))
    )
    (net (code "19") (name "DIR1") (class "Default")
      (node (ref "IC7") (pin "9") (pinfunction "A6_9") (pintype "bidirectional"))
      (node (ref "J10") (pin "3") (pinfunction "3_3") (pintype "bidirectional"))
    )
    (net (code "20") (name "DIR2") (class "Default")
      (node (ref "IC7") (pin "10") (pinfunction "A7_10") (pintype "bidirectional"))
      (node (ref "J7") (pin "3") (pinfunction "3_3") (pintype "bidirectional"))
    )
    (net (code "21") (name "ENABLE0") (class "Default")
      (node (ref "J12") (pin "5") (pinfunction "5_5") (pintype "bidirectional"))
      (node (ref "U5") (pin "6") (pinfunction "IO0_6") (pintype "bidirectional"))
    )
    (net (code "22") (name "ENABLE1") (class "Default")
      (node (ref "J10") (pin "5") (pinfunction "5_5") (pintype "bidirectional"))
      (node (ref "U5") (pin "7") (pinfunction "IO1_7") (pintype "bidirectional"))
    )
    (net (code "23") (name "ENABLE2") (class "Default")
      (node (ref "J7") (pin "5") (pinfunction "5_5") (pintype "bidirectional"))
      (node (ref "U5") (pin "9") (pinfunction "IO2_9") (pintype "bidirectional"))
    )
    (net (code "24") (name "FROMDET0") (class "Default")
      (node (ref "IC9") (pin "3") (pinfunction "A0_3") (pintype "bidirectional"))
      (node (ref "J9") (pin "P$8") (pinfunction "8_P$8") (pintype "bidirectional"))
    )
    (net (code "25") (name "FROMDET1") (class "Default")
      (node (ref "IC9") (pin "4") (pinfunction "A1_4") (pintype "bidirectional"))
      (node (ref "J9") (pin "P$7") (pinfunction "7_P$7") (pintype "bidirectional"))
    )
    (net (code "26") (name "FROMDET2") (class "Default")
      (node (ref "IC9") (pin "5") (pinfunction "A2_5") (pintype "bidirectional"))
      (node (ref "J9") (pin "P$6") (pinfunction "6_P$6") (pintype "bidirectional"))
    )
    (net (code "27") (name "FROMDET3") (class "Default")
      (node (ref "IC9") (pin "6") (pinfunction "A3_6") (pintype "bidirectional"))
      (node (ref "J9") (pin "P$5") (pinfunction "5_P$5") (pintype "bidirectional"))
    )
    (net (code "28") (name "GND") (class "Default")
      (node (ref "C1") (pin "2") (pinfunction "P$2_2") (pintype "bidirectional"))
      (node (ref "C10") (pin "2") (pinfunction "P$2_2") (pintype "bidirectional"))
      (node (ref "C12") (pin "1") (pinfunction "P$1_1") (pintype "bidirectional"))
      (node (ref "C13") (pin "1") (pinfunction "P$1_1") (pintype "bidirectional"))
      (node (ref "C14") (pin "1") (pinfunction "P$1_1") (pintype "bidirectional"))
      (node (ref "C15") (pin "1") (pinfunction "P$1_1") (pintype "bidirectional"))
      (node (ref "C16") (pin "1") (pinfunction "P$1_1") (pintype "bidirectional"))
      (node (ref "C17") (pin "1") (pinfunction "P$1_1") (pintype "bidirectional"))
      (node (ref "C18") (pin "1") (pinfunction "P$1_1") (pintype "bidirectional"))
      (node (ref "C19") (pin "1") (pinfunction "P$1_1") (pintype "bidirectional"))
      (node (ref "C20") (pin "1") (pinfunction "P$1_1") (pintype "bidirectional"))
      (node (ref "C21") (pin "2") (pinfunction "P$2_2") (pintype "bidirectional"))
      (node (ref "C22") (pin "1") (pinfunction "P$1_1") (pintype "bidirectional"))
      (node (ref "C23") (pin "1") (pinfunction "P$1_1") (pintype "bidirectional"))
      (node (ref "C24") (pin "1") (pinfunction "P$1_1") (pintype "bidirectional"))
      (node (ref "C25") (pin "2") (pinfunction "P$2_2") (pintype "bidirectional"))
      (node (ref "C26") (pin "1") (pinfunction "P$1_1") (pintype "bidirectional"))
      (node (ref "C27") (pin "1") (pinfunction "P$1_1") (pintype "bidirectional"))
      (node (ref "C28") (pin "1") (pinfunction "P$1_1") (pintype "bidirectional"))
      (node (ref "C29") (pin "2") (pinfunction "P$2_2") (pintype "bidirectional"))
      (node (ref "C3") (pin "2") (pinfunction "MINUS_2") (pintype "bidirectional"))
      (node (ref "C30") (pin "1") (pinfunction "P$1_1") (pintype "bidirectional"))
      (node (ref "C31") (pin "1") (pinfunction "P$1_1") (pintype "bidirectional"))
      (node (ref "C32") (pin "1") (pinfunction "P$1_1") (pintype "bidirectional"))
      (node (ref "C33") (pin "2") (pinfunction "P$2_2") (pintype "bidirectional"))
      (node (ref "C34") (pin "1") (pinfunction "P$1_1") (pintype "bidirectional"))
      (node (ref "C4") (pin "1") (pinfunction "P$1_1") (pintype "bidirectional"))
      (node (ref "C5") (pin "1") (pinfunction "P$1_1") (pintype "bidirectional"))
      (node (ref "C6") (pin "1") (pinfunction "P$1_1") (pintype "bidirectional"))
      (node (ref "C7") (pin "1") (pinfunction "P$1_1") (pintype "bidirectional"))
      (node (ref "C9") (pin "2") (pinfunction "P$2_2") (pintype "bidirectional"))
      (node (ref "D1") (pin "1") (pinfunction "ANODE_1") (pintype "bidirectional"))
      (node (ref "IC1") (pin "P$2") (pinfunction "GND_P$2") (pintype "bidirectional"))
      (node (ref "IC10") (pin "10") (pinfunction "GND_10") (pintype "bidirectional"))
      (node (ref "IC11") (pin "11") (pinfunction "GND1_11") (pintype "bidirectional"))
      (node (ref "IC11") (pin "12") (pinfunction "GND2_12") (pintype "bidirectional"))
      (node (ref "IC11") (pin "13") (pinfunction "GND3_13") (pintype "bidirectional"))
      (node (ref "IC11") (pin "22") (pinfunction "/OE_22") (pintype "bidirectional"))
      (node (ref "IC2") (pin "2") (pinfunction "GND_2") (pintype "bidirectional"))
      (node (ref "IC3") (pin "15") (pinfunction "GND_15") (pintype "power_in"))
      (node (ref "IC4") (pin "18") (pinfunction "GND1_18") (pintype "power_in"))
      (node (ref "IC4") (pin "30") (pinfunction "GND2_30") (pintype "power_in"))
      (node (ref "IC4") (pin "38") (pinfunction "GND3_38") (pintype "power_in"))
      (node (ref "IC4") (pin "8") (pinfunction "GND_8") (pintype "power_in"))
      (node (ref "IC5") (pin "11") (pinfunction "GND1_11") (pintype "bidirectional"))
      (node (ref "IC5") (pin "12") (pinfunction "GND2_12") (pintype "bidirectional"))
      (node (ref "IC5") (pin "13") (pinfunction "GND3_13") (pintype "bidirectional"))
      (node (ref "IC5") (pin "2") (pinfunction "DIR_2") (pintype "bidirectional"))
      (node (ref "IC5") (pin "22") (pinfunction "/OE_22") (pintype "bidirectional"))
      (node (ref "IC6") (pin "10") (pinfunction "GND_10") (pintype "bidirectional"))
      (node (ref "IC7") (pin "11") (pinfunction "GND1_11") (pintype "bidirectional"))
      (node (ref "IC7") (pin "12") (pinfunction "GND2_12") (pintype "bidirectional"))
      (node (ref "IC7") (pin "13") (pinfunction "GND3_13") (pintype "bidirectional"))
      (node (ref "IC7") (pin "2") (pinfunction "DIR_2") (pintype "bidirectional"))
      (node (ref "IC7") (pin "22") (pinfunction "/OE_22") (pintype "bidirectional"))
      (node (ref "IC8") (pin "10") (pinfunction "GND_10") (pintype "bidirectional"))
      (node (ref "IC9") (pin "11") (pinfunction "GND1_11") (pintype "bidirectional"))
      (node (ref "IC9") (pin "12") (pinfunction "GND2_12") (pintype "bidirectional"))
      (node (ref "IC9") (pin "13") (pinfunction "GND3_13") (pintype "bidirectional"))
      (node (ref "IC9") (pin "22") (pinfunction "/OE_22") (pintype "bidirectional"))
      (node (ref "J1") (pin "P$2") (pinfunction "2_P$2") (pintype "bidirectional"))
      (node (ref "J10") (pin "10") (pinfunction "10_10") (pintype "bidirectional"))
      (node (ref "J11") (pin "9") (pinfunction "9_9") (pintype "bidirectional"))
      (node (ref "J12") (pin "10") (pinfunction "10_10") (pintype "bidirectional"))
      (node (ref "J2") (pin "P$3") (pinfunction "3_P$3") (pintype "bidirectional"))
      (node (ref "J3") (pin "9") (pinfunction "9_9") (pintype "bidirectional"))
      (node (ref "J4") (pin "P$1") (pinfunction "1_P$1") (pintype "bidirectional"))
      (node (ref "J6") (pin "9") (pinfunction "9_9") (pintype "bidirectional"))
      (node (ref "J7") (pin "10") (pinfunction "10_10") (pintype "bidirectional"))
      (node (ref "J8") (pin "9") (pinfunction "9_9") (pintype "bidirectional"))
      (node (ref "J9") (pin "P$10") (pinfunction "10_P$10") (pintype "bidirectional"))
      (node (ref "J9") (pin "P$9") (pinfunction "9_P$9") (pintype "bidirectional"))
      (node (ref "JP1") (pin "6") (pinfunction "6_6") (pintype "passive"))
      (node (ref "LED1") (pin "1") (pinfunction "KATHODE_1") (pintype "bidirectional"))
      (node (ref "LJ1") (pin "L1") (pinfunction "L1_L1") (pintype "bidirectional"))
      (node (ref "LJ1") (pin "L2") (pinfunction "L2_L2") (pintype "bidirectional"))
      (node (ref "LJ1") (pin "L3") (pinfunction "L3_L3") (pintype "bidirectional"))
      (node (ref "LJ2") (pin "L1") (pinfunction "L1_L1") (pintype "bidirectional"))
      (node (ref "LJ2") (pin "L2") (pinfunction "L2_L2") (pintype "bidirectional"))
      (node (ref "LJ2") (pin "L3") (pinfunction "L3_L3") (pintype "bidirectional"))
      (node (ref "LJ3") (pin "L1") (pinfunction "L1_L1") (pintype "bidirectional"))
      (node (ref "LJ3") (pin "L2") (pinfunction "L2_L2") (pintype "bidirectional"))
      (node (ref "LJ3") (pin "L3") (pinfunction "L3_L3") (pintype "bidirectional"))
      (node (ref "LJ4") (pin "L1") (pinfunction "L1_L1") (pintype "bidirectional"))
      (node (ref "LJ4") (pin "L2") (pinfunction "L2_L2") (pintype "bidirectional"))
      (node (ref "LJ4") (pin "L3") (pinfunction "L3_L3") (pintype "bidirectional"))
      (node (ref "LJ5") (pin "L1") (pinfunction "L1_L1") (pintype "bidirectional"))
      (node (ref "LJ5") (pin "L2") (pinfunction "L2_L2") (pintype "bidirectional"))
      (node (ref "LJ5") (pin "L3") (pinfunction "L3_L3") (pintype "bidirectional"))
      (node (ref "LJ6") (pin "L1") (pinfunction "L1_L1") (pintype "bidirectional"))
      (node (ref "LJ6") (pin "L2") (pinfunction "L2_L2") (pintype "bidirectional"))
      (node (ref "LJ6") (pin "L3") (pinfunction "L3_L3") (pintype "bidirectional"))
      (node (ref "R10") (pin "1") (pinfunction "P$1_1") (pintype "bidirectional"))
      (node (ref "R35") (pin "1") (pinfunction "P$1_1") (pintype "bidirectional"))
      (node (ref "R44") (pin "1") (pinfunction "P$1_1") (pintype "bidirectional"))
      (node (ref "R45") (pin "1") (pinfunction "P$1_1") (pintype "bidirectional"))
      (node (ref "R46") (pin "1") (pinfunction "P$1_1") (pintype "bidirectional"))
      (node (ref "R47") (pin "1") (pinfunction "P$1_1") (pintype "bidirectional"))
      (node (ref "R48") (pin "1") (pinfunction "P$1_1") (pintype "bidirectional"))
      (node (ref "R49") (pin "1") (pinfunction "P$1_1") (pintype "bidirectional"))
      (node (ref "R58") (pin "1") (pinfunction "P$1_1") (pintype "bidirectional"))
      (node (ref "R67") (pin "1") (pinfunction "P$1_1") (pintype "bidirectional"))
      (node (ref "R68") (pin "1") (pinfunction "P$1_1") (pintype "bidirectional"))
      (node (ref "R69") (pin "1") (pinfunction "P$1_1") (pintype "bidirectional"))
      (node (ref "R7") (pin "2") (pinfunction "P$2_2") (pintype "bidirectional"))
      (node (ref "R70") (pin "1") (pinfunction "P$1_1") (pintype "bidirectional"))
      (node (ref "R71") (pin "1") (pinfunction "P$1_1") (pintype "bidirectional"))
      (node (ref "R72") (pin "1") (pinfunction "P$1_1") (pintype "bidirectional"))
      (node (ref "R82") (pin "1") (pinfunction "P$1_1") (pintype "bidirectional"))
      (node (ref "R9") (pin "1") (pinfunction "P$1_1") (pintype "bidirectional"))
      (node (ref "R91") (pin "1") (pinfunction "P$1_1") (pintype "bidirectional"))
      (node (ref "R92") (pin "1") (pinfunction "P$1_1") (pintype "bidirectional"))
      (node (ref "R93") (pin "1") (pinfunction "P$1_1") (pintype "bidirectional"))
      (node (ref "R94") (pin "1") (pinfunction "P$1_1") (pintype "bidirectional"))
      (node (ref "R95") (pin "1") (pinfunction "P$1_1") (pintype "bidirectional"))
      (node (ref "R96") (pin "1") (pinfunction "P$1_1") (pintype "bidirectional"))
      (node (ref "U1") (pin "3") (pinfunction "GND1_3") (pintype "bidirectional"))
      (node (ref "U1") (pin "6") (pinfunction "GND2_6") (pintype "bidirectional"))
      (node (ref "U1") (pin "7") (pinfunction "GND3_7") (pintype "bidirectional"))
      (node (ref "U2") (pin "4") (pinfunction "GND_4") (pintype "bidirectional"))
      (node (ref "U3") (pin "8") (pinfunction "GND_8") (pintype "bidirectional"))
      (node (ref "U4") (pin "8") (pinfunction "GND_8") (pintype "bidirectional"))
      (node (ref "U5") (pin "8") (pinfunction "GND_8") (pintype "bidirectional"))
      (node (ref "U6") (pin "8") (pinfunction "GND_8") (pintype "bidirectional"))
      (node (ref "U7") (pin "8") (pinfunction "GND_8") (pintype "bidirectional"))
      (node (ref "U8") (pin "8") (pinfunction "GND_8") (pintype "bidirectional"))
    )
    (net (code "29") (name "HOME0") (class "Default")
      (node (ref "IC11") (pin "8") (pinfunction "A5_8") (pintype "bidirectional"))
      (node (ref "J12") (pin "15") (pinfunction "15_15") (pintype "bidirectional"))
    )
    (net (code "30") (name "HOME1") (class "Default")
      (node (ref "IC11") (pin "9") (pinfunction "A6_9") (pintype "bidirectional"))
      (node (ref "J10") (pin "15") (pinfunction "15_15") (pintype "bidirectional"))
    )
    (net (code "31") (name "HOME2") (class "Default")
      (node (ref "IC11") (pin "10") (pinfunction "A7_10") (pintype "bidirectional"))
      (node (ref "J7") (pin "15") (pinfunction "15_15") (pintype "bidirectional"))
    )
    (net (code "32") (name "LIM+0") (class "Default")
      (node (ref "J12") (pin "11") (pinfunction "11_11") (pintype "bidirectional"))
      (node (ref "U7") (pin "6") (pinfunction "IO0_6") (pintype "bidirectional"))
    )
    (net (code "33") (name "LIM+1") (class "Default")
      (node (ref "J10") (pin "11") (pinfunction "11_11") (pintype "bidirectional"))
      (node (ref "U7") (pin "9") (pinfunction "IO2_9") (pintype "bidirectional"))
    )
    (net (code "34") (name "LIM+2") (class "Default")
      (node (ref "J7") (pin "11") (pinfunction "11_11") (pintype "bidirectional"))
      (node (ref "U7") (pin "11") (pinfunction "IO4_11") (pintype "bidirectional"))
    )
    (net (code "35") (name "LIM-0") (class "Default")
      (node (ref "J12") (pin "13") (pinfunction "13_13") (pintype "bidirectional"))
      (node (ref "U7") (pin "7") (pinfunction "IO1_7") (pintype "bidirectional"))
    )
    (net (code "36") (name "LIM-1") (class "Default")
      (node (ref "J10") (pin "13") (pinfunction "13_13") (pintype "bidirectional"))
      (node (ref "U7") (pin "10") (pinfunction "IO3_10") (pintype "bidirectional"))
    )
    (net (code "37") (name "LIM-2") (class "Default")
      (node (ref "J7") (pin "13") (pinfunction "13_13") (pintype "bidirectional"))
      (node (ref "U7") (pin "12") (pinfunction "IO5_12") (pintype "bidirectional"))
    )
    (net (code "38") (name "Net-(C2-P$1)") (class "Default")
      (node (ref "C2") (pin "1") (pinfunction "P$1_1") (pintype "bidirectional"))
      (node (ref "U1") (pin "4") (pinfunction "BYP_4") (pintype "bidirectional"))
    )
    (net (code "39") (name "Net-(C8-P$1)") (class "Default")
      (node (ref "C8") (pin "1") (pinfunction "P$1_1") (pintype "bidirectional"))
      (node (ref "IC3") (pin "1") (pinfunction "C1+_1") (pintype "bidirectional"))
    )
    (net (code "40") (name "Net-(C8-P$2)") (class "Default")
      (node (ref "C8") (pin "2") (pinfunction "P$2_2") (pintype "bidirectional"))
      (node (ref "IC3") (pin "3") (pinfunction "C1-_3") (pintype "bidirectional"))
    )
    (net (code "41") (name "Net-(C9-P$1)") (class "Default")
      (node (ref "C9") (pin "1") (pinfunction "P$1_1") (pintype "bidirectional"))
      (node (ref "IC3") (pin "2") (pinfunction "V+_2") (pintype "bidirectional"))
    )
    (net (code "42") (name "Net-(C10-P$1)") (class "Default")
      (node (ref "C10") (pin "1") (pinfunction "P$1_1") (pintype "bidirectional"))
      (node (ref "IC3") (pin "6") (pinfunction "V-_6") (pintype "bidirectional"))
    )
    (net (code "43") (name "Net-(C11-P$1)") (class "Default")
      (node (ref "C11") (pin "1") (pinfunction "P$1_1") (pintype "bidirectional"))
      (node (ref "IC3") (pin "4") (pinfunction "C2+_4") (pintype "bidirectional"))
    )
    (net (code "44") (name "Net-(C11-P$2)") (class "Default")
      (node (ref "C11") (pin "2") (pinfunction "P$2_2") (pintype "bidirectional"))
      (node (ref "IC3") (pin "5") (pinfunction "C2-_5") (pintype "bidirectional"))
    )
    (net (code "45") (name "Net-(C16-P$2)") (class "Default")
      (node (ref "C16") (pin "2") (pinfunction "P$2_2") (pintype "bidirectional"))
      (node (ref "IC4") (pin "37") (pinfunction "PR1(XT1)_37") (pintype "bidirectional"))
      (node (ref "Q1") (pin "1") (pinfunction "1_1") (pintype "passive"))
    )
    (net (code "46") (name "Net-(C17-P$2)") (class "Default")
      (node (ref "C17") (pin "2") (pinfunction "P$2_2") (pintype "bidirectional"))
      (node (ref "IC4") (pin "36") (pinfunction "PR0(XT2)_36") (pintype "bidirectional"))
      (node (ref "Q1") (pin "2") (pinfunction "2_2") (pintype "passive"))
    )
    (net (code "47") (name "Net-(D1-KATHODE)") (class "Default")
      (node (ref "D1") (pin "3") (pinfunction "KATHODE_3") (pintype "bidirectional"))
      (node (ref "IC4") (pin "22") (pinfunction "PD2_22") (pintype "bidirectional"))
      (node (ref "R11") (pin "1") (pinfunction "P$1_1") (pintype "bidirectional"))
    )
    (net (code "48") (name "Net-(IC3A-R1IN)") (class "Default")
      (node (ref "IC3") (pin "13") (pinfunction "R1IN_13") (pintype "input"))
      (node (ref "J3") (pin "5") (pinfunction "5_5") (pintype "bidirectional"))
    )
    (net (code "49") (name "Net-(IC3A-R1OUT)") (class "Default")
      (node (ref "IC3") (pin "12") (pinfunction "R1OUT_12") (pintype "output"))
      (node (ref "R11") (pin "2") (pinfunction "P$2_2") (pintype "bidirectional"))
    )
    (net (code "50") (name "Net-(IC3A-R2IN)") (class "Default")
      (node (ref "IC3") (pin "8") (pinfunction "R2IN_8") (pintype "input"))
      (node (ref "R10") (pin "2") (pinfunction "P$2_2") (pintype "bidirectional"))
    )
    (net (code "51") (name "Net-(IC3A-T1IN)") (class "Default")
      (node (ref "IC3") (pin "11") (pinfunction "T1IN_11") (pintype "input"))
      (node (ref "IC4") (pin "23") (pinfunction "PD3_23") (pintype "bidirectional"))
    )
    (net (code "52") (name "Net-(IC3A-T1OUT)") (class "Default")
      (node (ref "IC3") (pin "14") (pinfunction "T1OUT_14") (pintype "output"))
      (node (ref "J3") (pin "3") (pinfunction "3_3") (pintype "bidirectional"))
    )
    (net (code "53") (name "Net-(IC3A-T2IN)") (class "Default")
      (node (ref "IC3") (pin "10") (pinfunction "T2IN_10") (pintype "input"))
      (node (ref "R9") (pin "2") (pinfunction "P$2_2") (pintype "bidirectional"))
    )
    (net (code "54") (name "Net-(IC4-PC0)") (class "Default")
      (node (ref "IC4") (pin "10") (pinfunction "PC0_10") (pintype "bidirectional"))
      (node (ref "R3") (pin "2") (pinfunction "P$2_2") (pintype "bidirectional"))
      (node (ref "U2") (pin "1") (pinfunction "SX(SDA)_1") (pintype "bidirectional"))
    )
    (net (code "55") (name "Net-(IC4-PC1)") (class "Default")
      (node (ref "IC4") (pin "11") (pinfunction "PC1_11") (pintype "bidirectional"))
      (node (ref "R4") (pin "2") (pinfunction "P$2_2") (pintype "bidirectional"))
      (node (ref "U2") (pin "7") (pinfunction "SY(SCL)_7") (pintype "bidirectional"))
    )
    (net (code "56") (name "Net-(IC6-AN)") (class "Default")
      (node (ref "IC6") (pin "5") (pinfunction "AN_5") (pintype "bidirectional"))
      (node (ref "R30") (pin "1") (pinfunction "P$1_1") (pintype "bidirectional"))
      (node (ref "R38") (pin "1") (pinfunction "P$1_1") (pintype "bidirectional"))
      (node (ref "R45") (pin "2") (pinfunction "P$2_2") (pintype "bidirectional"))
    )
    (net (code "57") (name "Net-(IC6-AP)") (class "Default")
      (node (ref "IC6") (pin "4") (pinfunction "AP_4") (pintype "bidirectional"))
      (node (ref "R29") (pin "1") (pinfunction "P$1_1") (pintype "bidirectional"))
      (node (ref "R37") (pin "1") (pinfunction "P$1_1") (pintype "bidirectional"))
      (node (ref "R44") (pin "2") (pinfunction "P$2_2") (pintype "bidirectional"))
    )
    (net (code "58") (name "Net-(IC6-BN)") (class "Default")
      (node (ref "IC6") (pin "7") (pinfunction "BN_7") (pintype "bidirectional"))
      (node (ref "R32") (pin "1") (pinfunction "P$1_1") (pintype "bidirectional"))
      (node (ref "R40") (pin "1") (pinfunction "P$1_1") (pintype "bidirectional"))
      (node (ref "R47") (pin "2") (pinfunction "P$2_2") (pintype "bidirectional"))
    )
    (net (code "59") (name "Net-(IC6-BP)") (class "Default")
      (node (ref "IC6") (pin "6") (pinfunction "BP_6") (pintype "bidirectional"))
      (node (ref "R31") (pin "1") (pinfunction "P$1_1") (pintype "bidirectional"))
      (node (ref "R39") (pin "1") (pinfunction "P$1_1") (pintype "bidirectional"))
      (node (ref "R46") (pin "2") (pinfunction "P$2_2") (pintype "bidirectional"))
    )
    (net (code "60") (name "Net-(IC6-CN)") (class "Default")
      (node (ref "IC6") (pin "9") (pinfunction "CN_9") (pintype "bidirectional"))
      (node (ref "R34") (pin "1") (pinfunction "P$1_1") (pintype "bidirectional"))
      (node (ref "R42") (pin "1") (pinfunction "P$1_1") (pintype "bidirectional"))
      (node (ref "R49") (pin "2") (pinfunction "P$2_2") (pintype "bidirectional"))
    )
    (net (code "61") (name "Net-(IC6-CP)") (class "Default")
      (node (ref "IC6") (pin "8") (pinfunction "CP_8") (pintype "bidirectional"))
      (node (ref "R33") (pin "1") (pinfunction "P$1_1") (pintype "bidirectional"))
      (node (ref "R41") (pin "1") (pinfunction "P$1_1") (pintype "bidirectional"))
      (node (ref "R48") (pin "2") (pinfunction "P$2_2") (pintype "bidirectional"))
    )
    (net (code "62") (name "Net-(IC6-MA)") (class "Default")
      (node (ref "IC6") (pin "3") (pinfunction "MA_3") (pintype "bidirectional"))
      (node (ref "R36") (pin "2") (pinfunction "P$2_2") (pintype "bidirectional"))
    )
    (net (code "63") (name "Net-(IC6-SLI)") (class "Default")
      (node (ref "IC6") (pin "2") (pinfunction "SLI_2") (pintype "bidirectional"))
      (node (ref "R35") (pin "2") (pinfunction "P$2_2") (pintype "bidirectional"))
    )
    (net (code "64") (name "Net-(IC6-TPI)") (class "Default")
      (node (ref "IC6") (pin "20") (pinfunction "TPI_20") (pintype "bidirectional"))
      (node (ref "R28") (pin "2") (pinfunction "P$2_2") (pintype "bidirectional"))
    )
    (net (code "65") (name "Net-(IC8-AN)") (class "Default")
      (node (ref "IC8") (pin "5") (pinfunction "AN_5") (pintype "bidirectional"))
      (node (ref "R53") (pin "1") (pinfunction "P$1_1") (pintype "bidirectional"))
      (node (ref "R61") (pin "1") (pinfunction "P$1_1") (pintype "bidirectional"))
      (node (ref "R68") (pin "2") (pinfunction "P$2_2") (pintype "bidirectional"))
    )
    (net (code "66") (name "Net-(IC8-AP)") (class "Default")
      (node (ref "IC8") (pin "4") (pinfunction "AP_4") (pintype "bidirectional"))
      (node (ref "R52") (pin "1") (pinfunction "P$1_1") (pintype "bidirectional"))
      (node (ref "R60") (pin "1") (pinfunction "P$1_1") (pintype "bidirectional"))
      (node (ref "R67") (pin "2") (pinfunction "P$2_2") (pintype "bidirectional"))
    )
    (net (code "67") (name "Net-(IC8-BN)") (class "Default")
      (node (ref "IC8") (pin "7") (pinfunction "BN_7") (pintype "bidirectional"))
      (node (ref "R55") (pin "1") (pinfunction "P$1_1") (pintype "bidirectional"))
      (node (ref "R63") (pin "1") (pinfunction "P$1_1") (pintype "bidirectional"))
      (node (ref "R70") (pin "2") (pinfunction "P$2_2") (pintype "bidirectional"))
    )
    (net (code "68") (name "Net-(IC8-BP)") (class "Default")
      (node (ref "IC8") (pin "6") (pinfunction "BP_6") (pintype "bidirectional"))
      (node (ref "R54") (pin "1") (pinfunction "P$1_1") (pintype "bidirectional"))
      (node (ref "R62") (pin "1") (pinfunction "P$1_1") (pintype "bidirectional"))
      (node (ref "R69") (pin "2") (pinfunction "P$2_2") (pintype "bidirectional"))
    )
    (net (code "69") (name "Net-(IC8-CN)") (class "Default")
      (node (ref "IC8") (pin "9") (pinfunction "CN_9") (pintype "bidirectional"))
      (node (ref "R57") (pin "1") (pinfunction "P$1_1") (pintype "bidirectional"))
      (node (ref "R65") (pin "1") (pinfunction "P$1_1") (pintype "bidirectional"))
      (node (ref "R72") (pin "2") (pinfunction "P$2_2") (pintype "bidirectional"))
    )
    (net (code "70") (name "Net-(IC8-CP)") (class "Default")
      (node (ref "IC8") (pin "8") (pinfunction "CP_8") (pintype "bidirectional"))
      (node (ref "R56") (pin "1") (pinfunction "P$1_1") (pintype "bidirectional"))
      (node (ref "R64") (pin "1") (pinfunction "P$1_1") (pintype "bidirectional"))
      (node (ref "R71") (pin "2") (pinfunction "P$2_2") (pintype "bidirectional"))
    )
    (net (code "71") (name "Net-(IC8-MA)") (class "Default")
      (node (ref "IC8") (pin "3") (pinfunction "MA_3") (pintype "bidirectional"))
      (node (ref "R59") (pin "2") (pinfunction "P$2_2") (pintype "bidirectional"))
    )
    (net (code "72") (name "Net-(IC8-SLI)") (class "Default")
      (node (ref "IC8") (pin "2") (pinfunction "SLI_2") (pintype "bidirectional"))
      (node (ref "R58") (pin "2") (pinfunction "P$2_2") (pintype "bidirectional"))
    )
    (net (code "73") (name "Net-(IC8-TPI)") (class "Default")
      (node (ref "IC8") (pin "20") (pinfunction "TPI_20") (pintype "bidirectional"))
      (node (ref "R51") (pin "2") (pinfunction "P$2_2") (pintype "bidirectional"))
    )
    (net (code "74") (name "Net-(IC9-DIR)") (class "Default")
      (node (ref "IC9") (pin "2") (pinfunction "DIR_2") (pintype "bidirectional"))
      (node (ref "R73") (pin "2") (pinfunction "P$2_2") (pintype "bidirectional"))
    )
    (net (code "75") (name "Net-(IC10-AN)") (class "Default")
      (node (ref "IC10") (pin "5") (pinfunction "AN_5") (pintype "bidirectional"))
      (node (ref "R77") (pin "1") (pinfunction "P$1_1") (pintype "bidirectional"))
      (node (ref "R85") (pin "1") (pinfunction "P$1_1") (pintype "bidirectional"))
      (node (ref "R92") (pin "2") (pinfunction "P$2_2") (pintype "bidirectional"))
    )
    (net (code "76") (name "Net-(IC10-AP)") (class "Default")
      (node (ref "IC10") (pin "4") (pinfunction "AP_4") (pintype "bidirectional"))
      (node (ref "R76") (pin "1") (pinfunction "P$1_1") (pintype "bidirectional"))
      (node (ref "R84") (pin "1") (pinfunction "P$1_1") (pintype "bidirectional"))
      (node (ref "R91") (pin "2") (pinfunction "P$2_2") (pintype "bidirectional"))
    )
    (net (code "77") (name "Net-(IC10-BN)") (class "Default")
      (node (ref "IC10") (pin "7") (pinfunction "BN_7") (pintype "bidirectional"))
      (node (ref "R79") (pin "1") (pinfunction "P$1_1") (pintype "bidirectional"))
      (node (ref "R87") (pin "1") (pinfunction "P$1_1") (pintype "bidirectional"))
      (node (ref "R94") (pin "2") (pinfunction "P$2_2") (pintype "bidirectional"))
    )
    (net (code "78") (name "Net-(IC10-BP)") (class "Default")
      (node (ref "IC10") (pin "6") (pinfunction "BP_6") (pintype "bidirectional"))
      (node (ref "R78") (pin "1") (pinfunction "P$1_1") (pintype "bidirectional"))
      (node (ref "R86") (pin "1") (pinfunction "P$1_1") (pintype "bidirectional"))
      (node (ref "R93") (pin "2") (pinfunction "P$2_2") (pintype "bidirectional"))
    )
    (net (code "79") (name "Net-(IC10-CN)") (class "Default")
      (node (ref "IC10") (pin "9") (pinfunction "CN_9") (pintype "bidirectional"))
      (node (ref "R81") (pin "1") (pinfunction "P$1_1") (pintype "bidirectional"))
      (node (ref "R89") (pin "1") (pinfunction "P$1_1") (pintype "bidirectional"))
      (node (ref "R96") (pin "2") (pinfunction "P$2_2") (pintype "bidirectional"))
    )
    (net (code "80") (name "Net-(IC10-CP)") (class "Default")
      (node (ref "IC10") (pin "8") (pinfunction "CP_8") (pintype "bidirectional"))
      (node (ref "R80") (pin "1") (pinfunction "P$1_1") (pintype "bidirectional"))
      (node (ref "R88") (pin "1") (pinfunction "P$1_1") (pintype "bidirectional"))
      (node (ref "R95") (pin "2") (pinfunction "P$2_2") (pintype "bidirectional"))
    )
    (net (code "81") (name "Net-(IC10-MA)") (class "Default")
      (node (ref "IC10") (pin "3") (pinfunction "MA_3") (pintype "bidirectional"))
      (node (ref "R83") (pin "2") (pinfunction "P$2_2") (pintype "bidirectional"))
    )
    (net (code "82") (name "Net-(IC10-SLI)") (class "Default")
      (node (ref "IC10") (pin "2") (pinfunction "SLI_2") (pintype "bidirectional"))
      (node (ref "R82") (pin "2") (pinfunction "P$2_2") (pintype "bidirectional"))
    )
    (net (code "83") (name "Net-(IC10-TPI)") (class "Default")
      (node (ref "IC10") (pin "20") (pinfunction "TPI_20") (pintype "bidirectional"))
      (node (ref "R75") (pin "2") (pinfunction "P$2_2") (pintype "bidirectional"))
    )
    (net (code "84") (name "Net-(IC11-DIR)") (class "Default")
      (node (ref "IC11") (pin "2") (pinfunction "DIR_2") (pintype "bidirectional"))
      (node (ref "R97") (pin "2") (pinfunction "P$2_2") (pintype "bidirectional"))
    )
    (net (code "85") (name "Net-(J2-2)") (class "Default")
      (node (ref "J2") (pin "P$2") (pinfunction "2_P$2") (pintype "bidirectional"))
      (node (ref "R2") (pin "2") (pinfunction "P$2_2") (pintype "bidirectional"))
    )
    (net (code "86") (name "Net-(J5-1)") (class "Default")
      (node (ref "J5") (pin "P$1") (pinfunction "1_P$1") (pintype "bidirectional"))
      (node (ref "U4") (pin "6") (pinfunction "IO0_6") (pintype "bidirectional"))
    )
    (net (code "87") (name "Net-(J5-2)") (class "Default")
      (node (ref "J5") (pin "P$2") (pinfunction "2_P$2") (pintype "bidirectional"))
      (node (ref "R24") (pin "2") (pinfunction "P$2_2") (pintype "bidirectional"))
    )
    (net (code "88") (name "Net-(J5-3)") (class "Default")
      (node (ref "J5") (pin "P$3") (pinfunction "3_P$3") (pintype "bidirectional"))
      (node (ref "U4") (pin "7") (pinfunction "IO1_7") (pintype "bidirectional"))
    )
    (net (code "89") (name "Net-(J5-4)") (class "Default")
      (node (ref "J5") (pin "P$4") (pinfunction "4_P$4") (pintype "bidirectional"))
      (node (ref "R23") (pin "2") (pinfunction "P$2_2") (pintype "bidirectional"))
    )
    (net (code "90") (name "Net-(J5-5)") (class "Default")
      (node (ref "J5") (pin "P$5") (pinfunction "5_P$5") (pintype "bidirectional"))
      (node (ref "U4") (pin "9") (pinfunction "IO2_9") (pintype "bidirectional"))
    )
    (net (code "91") (name "Net-(J5-6)") (class "Default")
      (node (ref "J5") (pin "P$6") (pinfunction "6_P$6") (pintype "bidirectional"))
      (node (ref "R22") (pin "2") (pinfunction "P$2_2") (pintype "bidirectional"))
    )
    (net (code "92") (name "Net-(J5-7)") (class "Default")
      (node (ref "J5") (pin "P$7") (pinfunction "7_P$7") (pintype "bidirectional"))
      (node (ref "U4") (pin "10") (pinfunction "IO3_10") (pintype "bidirectional"))
    )
    (net (code "93") (name "Net-(J5-8)") (class "Default")
      (node (ref "J5") (pin "P$8") (pinfunction "8_P$8") (pintype "bidirectional"))
      (node (ref "R21") (pin "2") (pinfunction "P$2_2") (pintype "bidirectional"))
    )
    (net (code "94") (name "Net-(J5-9)") (class "Default")
      (node (ref "J5") (pin "P$9") (pinfunction "9_P$9") (pintype "bidirectional"))
      (node (ref "U4") (pin "11") (pinfunction "IO4_11") (pintype "bidirectional"))
    )
    (net (code "95") (name "Net-(J5-10)") (class "Default")
      (node (ref "J5") (pin "P$10") (pinfunction "10_P$10") (pintype "bidirectional"))
      (node (ref "R20") (pin "2") (pinfunction "P$2_2") (pintype "bidirectional"))
    )
    (net (code "96") (name "Net-(J6-Pad3)") (class "Default")
      (node (ref "J6") (pin "3") (pinfunction "3_3") (pintype "bidirectional"))
      (node (ref "J7") (pin "8") (pinfunction "8_8") (pintype "bidirectional"))
    )
    (net (code "97") (name "Net-(J6-Pad5)") (class "Default")
      (node (ref "J6") (pin "5") (pinfunction "5_5") (pintype "bidirectional"))
      (node (ref "J7") (pin "6") (pinfunction "6_6") (pintype "bidirectional"))
    )
    (net (code "98") (name "Net-(J10-Pad6)") (class "Default")
      (node (ref "J10") (pin "6") (pinfunction "6_6") (pintype "bidirectional"))
      (node (ref "J8") (pin "5") (pinfunction "5_5") (pintype "bidirectional"))
    )
    (net (code "99") (name "Net-(J10-Pad8)") (class "Default")
      (node (ref "J10") (pin "8") (pinfunction "8_8") (pintype "bidirectional"))
      (node (ref "J8") (pin "3") (pinfunction "3_3") (pintype "bidirectional"))
    )
    (net (code "100") (name "Net-(J11-Pad3)") (class "Default")
      (node (ref "J11") (pin "3") (pinfunction "3_3") (pintype "bidirectional"))
      (node (ref "J12") (pin "8") (pinfunction "8_8") (pintype "bidirectional"))
    )
    (net (code "101") (name "Net-(J11-Pad5)") (class "Default")
      (node (ref "J11") (pin "5") (pinfunction "5_5") (pintype "bidirectional"))
      (node (ref "J12") (pin "6") (pinfunction "6_6") (pintype "bidirectional"))
    )
    (net (code "102") (name "Net-(LED1-ANODE)") (class "Default")
      (node (ref "LED1") (pin "2") (pinfunction "ANODE_2") (pintype "bidirectional"))
      (node (ref "R1") (pin "1") (pinfunction "P$1_1") (pintype "bidirectional"))
      (node (ref "R2") (pin "1") (pinfunction "P$1_1") (pintype "bidirectional"))
    )
    (net (code "103") (name "Net-(R25-P$1)") (class "Default")
      (node (ref "R25") (pin "1") (pinfunction "P$1_1") (pintype "bidirectional"))
      (node (ref "U3") (pin "15") (pinfunction "~{RESET}_15") (pintype "bidirectional"))
    )
    (net (code "104") (name "Net-(R26-P$1)") (class "Default")
      (node (ref "R26") (pin "1") (pinfunction "P$1_1") (pintype "bidirectional"))
      (node (ref "U4") (pin "15") (pinfunction "~{RESET}_15") (pintype "bidirectional"))
    )
    (net (code "105") (name "Net-(R27-P$1)") (class "Default")
      (node (ref "R27") (pin "1") (pinfunction "P$1_1") (pintype "bidirectional"))
      (node (ref "U5") (pin "15") (pinfunction "~{RESET}_15") (pintype "bidirectional"))
    )
    (net (code "106") (name "Net-(R37-P$2)") (class "Default")
      (node (ref "J7") (pin "12") (pinfunction "12_12") (pintype "bidirectional"))
      (node (ref "R37") (pin "2") (pinfunction "P$2_2") (pintype "bidirectional"))
    )
    (net (code "107") (name "Net-(R38-P$2)") (class "Default")
      (node (ref "J7") (pin "14") (pinfunction "14_14") (pintype "bidirectional"))
      (node (ref "R38") (pin "2") (pinfunction "P$2_2") (pintype "bidirectional"))
    )
    (net (code "108") (name "Net-(R39-P$2)") (class "Default")
      (node (ref "J7") (pin "16") (pinfunction "16_16") (pintype "bidirectional"))
      (node (ref "R39") (pin "2") (pinfunction "P$2_2") (pintype "bidirectional"))
    )
    (net (code "109") (name "Net-(R40-P$2)") (class "Default")
      (node (ref "J7") (pin "18") (pinfunction "18_18") (pintype "bidirectional"))
      (node (ref "R40") (pin "2") (pinfunction "P$2_2") (pintype "bidirectional"))
    )
    (net (code "110") (name "Net-(R41-P$2)") (class "Default")
      (node (ref "J7") (pin "20") (pinfunction "20_20") (pintype "bidirectional"))
      (node (ref "R41") (pin "2") (pinfunction "P$2_2") (pintype "bidirectional"))
    )
    (net (code "111") (name "Net-(R42-P$2)") (class "Default")
      (node (ref "J7") (pin "22") (pinfunction "22_22") (pintype "bidirectional"))
      (node (ref "R42") (pin "2") (pinfunction "P$2_2") (pintype "bidirectional"))
    )
    (net (code "112") (name "Net-(R43-P$2)") (class "Default")
      (node (ref "J7") (pin "21") (pinfunction "21_21") (pintype "bidirectional"))
      (node (ref "R43") (pin "2") (pinfunction "P$2_2") (pintype "bidirectional"))
    )
    (net (code "113") (name "Net-(R50-P$1)") (class "Default")
      (node (ref "R50") (pin "1") (pinfunction "P$1_1") (pintype "bidirectional"))
      (node (ref "U6") (pin "15") (pinfunction "~{RESET}_15") (pintype "bidirectional"))
    )
    (net (code "114") (name "Net-(R60-P$2)") (class "Default")
      (node (ref "J10") (pin "12") (pinfunction "12_12") (pintype "bidirectional"))
      (node (ref "R60") (pin "2") (pinfunction "P$2_2") (pintype "bidirectional"))
    )
    (net (code "115") (name "Net-(R61-P$2)") (class "Default")
      (node (ref "J10") (pin "14") (pinfunction "14_14") (pintype "bidirectional"))
      (node (ref "R61") (pin "2") (pinfunction "P$2_2") (pintype "bidirectional"))
    )
    (net (code "116") (name "Net-(R62-P$2)") (class "Default")
      (node (ref "J10") (pin "16") (pinfunction "16_16") (pintype "bidirectional"))
      (node (ref "R62") (pin "2") (pinfunction "P$2_2") (pintype "bidirectional"))
    )
    (net (code "117") (name "Net-(R63-P$2)") (class "Default")
      (node (ref "J10") (pin "18") (pinfunction "18_18") (pintype "bidirectional"))
      (node (ref "R63") (pin "2") (pinfunction "P$2_2") (pintype "bidirectional"))
    )
    (net (code "118") (name "Net-(R64-P$2)") (class "Default")
      (node (ref "J10") (pin "20") (pinfunction "20_20") (pintype "bidirectional"))
      (node (ref "R64") (pin "2") (pinfunction "P$2_2") (pintype "bidirectional"))
    )
    (net (code "119") (name "Net-(R65-P$2)") (class "Default")
      (node (ref "J10") (pin "22") (pinfunction "22_22") (pintype "bidirectional"))
      (node (ref "R65") (pin "2") (pinfunction "P$2_2") (pintype "bidirectional"))
    )
    (net (code "120") (name "Net-(R66-P$2)") (class "Default")
      (node (ref "J10") (pin "21") (pinfunction "21_21") (pintype "bidirectional"))
      (node (ref "R66") (pin "2") (pinfunction "P$2_2") (pintype "bidirectional"))
    )
    (net (code "121") (name "Net-(R74-P$1)") (class "Default")
      (node (ref "R74") (pin "1") (pinfunction "P$1_1") (pintype "bidirectional"))
      (node (ref "U7") (pin "15") (pinfunction "~{RESET}_15") (pintype "bidirectional"))
    )
    (net (code "122") (name "Net-(R84-P$2)") (class "Default")
      (node (ref "J12") (pin "12") (pinfunction "12_12") (pintype "bidirectional"))
      (node (ref "R84") (pin "2") (pinfunction "P$2_2") (pintype "bidirectional"))
    )
    (net (code "123") (name "Net-(R85-P$2)") (class "Default")
      (node (ref "J12") (pin "14") (pinfunction "14_14") (pintype "bidirectional"))
      (node (ref "R85") (pin "2") (pinfunction "P$2_2") (pintype "bidirectional"))
    )
    (net (code "124") (name "Net-(R86-P$2)") (class "Default")
      (node (ref "J12") (pin "16") (pinfunction "16_16") (pintype "bidirectional"))
      (node (ref "R86") (pin "2") (pinfunction "P$2_2") (pintype "bidirectional"))
    )
    (net (code "125") (name "Net-(R87-P$2)") (class "Default")
      (node (ref "J12") (pin "18") (pinfunction "18_18") (pintype "bidirectional"))
      (node (ref "R87") (pin "2") (pinfunction "P$2_2") (pintype "bidirectional"))
    )
    (net (code "126") (name "Net-(R88-P$2)") (class "Default")
      (node (ref "J12") (pin "20") (pinfunction "20_20") (pintype "bidirectional"))
      (node (ref "R88") (pin "2") (pinfunction "P$2_2") (pintype "bidirectional"))
    )
    (net (code "127") (name "Net-(R89-P$2)") (class "Default")
      (node (ref "J12") (pin "22") (pinfunction "22_22") (pintype "bidirectional"))
      (node (ref "R89") (pin "2") (pinfunction "P$2_2") (pintype "bidirectional"))
    )
    (net (code "128") (name "Net-(R90-P$2)") (class "Default")
      (node (ref "J12") (pin "21") (pinfunction "21_21") (pintype "bidirectional"))
      (node (ref "R90") (pin "2") (pinfunction "P$2_2") (pintype "bidirectional"))
    )
    (net (code "129") (name "Net-(R98-P$1)") (class "Default")
      (node (ref "R98") (pin "1") (pinfunction "P$1_1") (pintype "bidirectional"))
      (node (ref "U8") (pin "15") (pinfunction "~{RESET}_15") (pintype "bidirectional"))
    )
    (net (code "130") (name "Net-(U3-A0)") (class "Default")
      (node (ref "LJ1") (pin "1") (pinfunction "1_1") (pintype "bidirectional"))
      (node (ref "U3") (pin "3") (pinfunction "A0_3") (pintype "bidirectional"))
    )
    (net (code "131") (name "Net-(U3-A1)") (class "Default")
      (node (ref "LJ1") (pin "2") (pinfunction "2_2") (pintype "bidirectional"))
      (node (ref "U3") (pin "4") (pinfunction "A1_4") (pintype "bidirectional"))
    )
    (net (code "132") (name "Net-(U3-A2)") (class "Default")
      (node (ref "LJ1") (pin "3") (pinfunction "3_3") (pintype "bidirectional"))
      (node (ref "U3") (pin "5") (pinfunction "A2_5") (pintype "bidirectional"))
    )
    (net (code "133") (name "Net-(U4-A0)") (class "Default")
      (node (ref "LJ2") (pin "1") (pinfunction "1_1") (pintype "bidirectional"))
      (node (ref "U4") (pin "3") (pinfunction "A0_3") (pintype "bidirectional"))
    )
    (net (code "134") (name "Net-(U4-A1)") (class "Default")
      (node (ref "LJ2") (pin "2") (pinfunction "2_2") (pintype "bidirectional"))
      (node (ref "U4") (pin "4") (pinfunction "A1_4") (pintype "bidirectional"))
    )
    (net (code "135") (name "Net-(U4-A2)") (class "Default")
      (node (ref "LJ2") (pin "3") (pinfunction "3_3") (pintype "bidirectional"))
      (node (ref "U4") (pin "5") (pinfunction "A2_5") (pintype "bidirectional"))
    )
    (net (code "136") (name "Net-(U5-A0)") (class "Default")
      (node (ref "LJ3") (pin "1") (pinfunction "1_1") (pintype "bidirectional"))
      (node (ref "U5") (pin "3") (pinfunction "A0_3") (pintype "bidirectional"))
    )
    (net (code "137") (name "Net-(U5-A1)") (class "Default")
      (node (ref "LJ3") (pin "2") (pinfunction "2_2") (pintype "bidirectional"))
      (node (ref "U5") (pin "4") (pinfunction "A1_4") (pintype "bidirectional"))
    )
    (net (code "138") (name "Net-(U5-A2)") (class "Default")
      (node (ref "LJ3") (pin "3") (pinfunction "3_3") (pintype "bidirectional"))
      (node (ref "U5") (pin "5") (pinfunction "A2_5") (pintype "bidirectional"))
    )
    (net (code "139") (name "Net-(U6-A0)") (class "Default")
      (node (ref "LJ4") (pin "1") (pinfunction "1_1") (pintype "bidirectional"))
      (node (ref "U6") (pin "3") (pinfunction "A0_3") (pintype "bidirectional"))
    )
    (net (code "140") (name "Net-(U6-A1)") (class "Default")
      (node (ref "LJ4") (pin "2") (pinfunction "2_2") (pintype "bidirectional"))
      (node (ref "U6") (pin "4") (pinfunction "A1_4") (pintype "bidirectional"))
    )
    (net (code "141") (name "Net-(U6-A2)") (class "Default")
      (node (ref "LJ4") (pin "3") (pinfunction "3_3") (pintype "bidirectional"))
      (node (ref "U6") (pin "5") (pinfunction "A2_5") (pintype "bidirectional"))
    )
    (net (code "142") (name "Net-(U7-A0)") (class "Default")
      (node (ref "LJ5") (pin "1") (pinfunction "1_1") (pintype "bidirectional"))
      (node (ref "U7") (pin "3") (pinfunction "A0_3") (pintype "bidirectional"))
    )
    (net (code "143") (name "Net-(U7-A1)") (class "Default")
      (node (ref "LJ5") (pin "2") (pinfunction "2_2") (pintype "bidirectional"))
      (node (ref "U7") (pin "4") (pinfunction "A1_4") (pintype "bidirectional"))
    )
    (net (code "144") (name "Net-(U7-A2)") (class "Default")
      (node (ref "LJ5") (pin "3") (pinfunction "3_3") (pintype "bidirectional"))
      (node (ref "U7") (pin "5") (pinfunction "A2_5") (pintype "bidirectional"))
    )
    (net (code "145") (name "Net-(U8-A0)") (class "Default")
      (node (ref "LJ6") (pin "1") (pinfunction "1_1") (pintype "bidirectional"))
      (node (ref "U8") (pin "3") (pinfunction "A0_3") (pintype "bidirectional"))
    )
    (net (code "146") (name "Net-(U8-A1)") (class "Default")
      (node (ref "LJ6") (pin "2") (pinfunction "2_2") (pintype "bidirectional"))
      (node (ref "U8") (pin "4") (pinfunction "A1_4") (pintype "bidirectional"))
    )
    (net (code "147") (name "Net-(U8-A2)") (class "Default")
      (node (ref "LJ6") (pin "3") (pinfunction "3_3") (pintype "bidirectional"))
      (node (ref "U8") (pin "5") (pinfunction "A2_5") (pintype "bidirectional"))
    )
    (net (code "148") (name "ON{slash}OFF0") (class "Default")
      (node (ref "J12") (pin "7") (pinfunction "7_7") (pintype "bidirectional"))
      (node (ref "U5") (pin "10") (pinfunction "IO3_10") (pintype "bidirectional"))
    )
    (net (code "149") (name "ON{slash}OFF1") (class "Default")
      (node (ref "J10") (pin "7") (pinfunction "7_7") (pintype "bidirectional"))
      (node (ref "U5") (pin "11") (pinfunction "IO4_11") (pintype "bidirectional"))
    )
    (net (code "150") (name "ON{slash}OFF2") (class "Default")
      (node (ref "J7") (pin "7") (pinfunction "7_7") (pintype "bidirectional"))
      (node (ref "U5") (pin "12") (pinfunction "IO5_12") (pintype "bidirectional"))
    )
    (net (code "151") (name "PA0") (class "Default")
      (node (ref "IC4") (pin "40") (pinfunction "PA0_40") (pintype "bidirectional"))
      (node (ref "IC9") (pin "21") (pinfunction "B0_21") (pintype "bidirectional"))
    )
    (net (code "152") (name "PA1") (class "Default")
      (node (ref "IC4") (pin "41") (pinfunction "PA1_41") (pintype "bidirectional"))
      (node (ref "IC9") (pin "20") (pinfunction "B1_20") (pintype "bidirectional"))
    )
    (net (code "153") (name "PA2") (class "Default")
      (node (ref "IC4") (pin "42") (pinfunction "PA2_42") (pintype "bidirectional"))
      (node (ref "IC9") (pin "19") (pinfunction "B2_19") (pintype "bidirectional"))
    )
    (net (code "154") (name "PA3") (class "Default")
      (node (ref "IC4") (pin "43") (pinfunction "PA3_43") (pintype "bidirectional"))
      (node (ref "IC9") (pin "18") (pinfunction "B3_18") (pintype "bidirectional"))
    )
    (net (code "155") (name "PA4") (class "Default")
      (node (ref "IC4") (pin "44") (pinfunction "PA4_44") (pintype "bidirectional"))
      (node (ref "IC5") (pin "17") (pinfunction "B4_17") (pintype "bidirectional"))
    )
    (net (code "156") (name "PA5") (class "Default")
      (node (ref "IC4") (pin "1") (pinfunction "PA5_1") (pintype "bidirectional"))
      (node (ref "IC5") (pin "16") (pinfunction "B5_16") (pintype "bidirectional"))
    )
    (net (code "157") (name "PA6") (class "Default")
      (node (ref "IC4") (pin "2") (pinfunction "PA6_2") (pintype "bidirectional"))
      (node (ref "IC5") (pin "15") (pinfunction "B6_15") (pintype "bidirectional"))
    )
    (net (code "158") (name "PA7") (class "Default")
      (node (ref "IC4") (pin "3") (pinfunction "PA7_3") (pintype "bidirectional"))
      (node (ref "IC5") (pin "14") (pinfunction "B7_14") (pintype "bidirectional"))
    )
    (net (code "159") (name "PB0") (class "Default")
      (node (ref "IC11") (pin "21") (pinfunction "B0_21") (pintype "bidirectional"))
      (node (ref "IC4") (pin "4") (pinfunction "PB0_4") (pintype "bidirectional"))
    )
    (net (code "160") (name "PB1") (class "Default")
      (node (ref "IC11") (pin "20") (pinfunction "B1_20") (pintype "bidirectional"))
      (node (ref "IC4") (pin "5") (pinfunction "PB1_5") (pintype "bidirectional"))
    )
    (net (code "161") (name "PB2") (class "Default")
      (node (ref "IC11") (pin "19") (pinfunction "B2_19") (pintype "bidirectional"))
      (node (ref "IC4") (pin "6") (pinfunction "PB2_6") (pintype "bidirectional"))
    )
    (net (code "162") (name "PB3") (class "Default")
      (node (ref "IC4") (pin "7") (pinfunction "PB3_7") (pintype "bidirectional"))
      (node (ref "R12") (pin "1") (pinfunction "P$1_1") (pintype "bidirectional"))
    )
    (net (code "163") (name "PC2") (class "Default")
      (node (ref "IC4") (pin "12") (pinfunction "PC2_12") (pintype "bidirectional"))
      (node (ref "IC5") (pin "21") (pinfunction "B0_21") (pintype "bidirectional"))
    )
    (net (code "164") (name "PC3") (class "Default")
      (node (ref "IC4") (pin "13") (pinfunction "PC3_13") (pintype "bidirectional"))
      (node (ref "IC5") (pin "20") (pinfunction "B1_20") (pintype "bidirectional"))
    )
    (net (code "165") (name "PC4") (class "Default")
      (node (ref "IC4") (pin "14") (pinfunction "PC4_14") (pintype "bidirectional"))
      (node (ref "IC5") (pin "19") (pinfunction "B2_19") (pintype "bidirectional"))
    )
    (net (code "166") (name "PC5") (class "Default")
      (node (ref "IC10") (pin "14") (pinfunction "MOSI_14") (pintype "bidirectional"))
      (node (ref "IC4") (pin "15") (pinfunction "PC5_15") (pintype "bidirectional"))
      (node (ref "IC6") (pin "14") (pinfunction "MOSI_14") (pintype "bidirectional"))
      (node (ref "IC8") (pin "14") (pinfunction "MOSI_14") (pintype "bidirectional"))
    )
    (net (code "167") (name "PC6") (class "Default")
      (node (ref "IC10") (pin "13") (pinfunction "MISO_13") (pintype "bidirectional"))
      (node (ref "IC4") (pin "16") (pinfunction "PC6_16") (pintype "bidirectional"))
      (node (ref "IC6") (pin "13") (pinfunction "MISO_13") (pintype "bidirectional"))
      (node (ref "IC8") (pin "13") (pinfunction "MISO_13") (pintype "bidirectional"))
    )
    (net (code "168") (name "PC7") (class "Default")
      (node (ref "IC10") (pin "15") (pinfunction "SCK_15") (pintype "bidirectional"))
      (node (ref "IC4") (pin "17") (pinfunction "PC7_17") (pintype "bidirectional"))
      (node (ref "IC6") (pin "15") (pinfunction "SCK_15") (pintype "bidirectional"))
      (node (ref "IC8") (pin "15") (pinfunction "SCK_15") (pintype "bidirectional"))
    )
    (net (code "169") (name "PD0") (class "Default")
      (node (ref "IC4") (pin "20") (pinfunction "PD0_20") (pintype "bidirectional"))
      (node (ref "IC7") (pin "21") (pinfunction "B0_21") (pintype "bidirectional"))
    )
    (net (code "170") (name "PD1") (class "Default")
      (node (ref "IC4") (pin "21") (pinfunction "PD1_21") (pintype "bidirectional"))
      (node (ref "IC7") (pin "20") (pinfunction "B1_20") (pintype "bidirectional"))
    )
    (net (code "171") (name "PD4") (class "Default")
      (node (ref "IC4") (pin "24") (pinfunction "PD4_24") (pintype "bidirectional"))
      (node (ref "IC7") (pin "17") (pinfunction "B4_17") (pintype "bidirectional"))
    )
    (net (code "172") (name "PD5") (class "Default")
      (node (ref "IC4") (pin "25") (pinfunction "PD5_25") (pintype "bidirectional"))
      (node (ref "IC7") (pin "16") (pinfunction "B5_16") (pintype "bidirectional"))
    )
    (net (code "173") (name "PD6") (class "Default")
      (node (ref "IC4") (pin "26") (pinfunction "PD6_26") (pintype "bidirectional"))
      (node (ref "IC7") (pin "15") (pinfunction "B6_15") (pintype "bidirectional"))
    )
    (net (code "174") (name "PD7") (class "Default")
      (node (ref "IC4") (pin "27") (pinfunction "PD7_27") (pintype "bidirectional"))
      (node (ref "IC7") (pin "14") (pinfunction "B7_14") (pintype "bidirectional"))
    )
    (net (code "175") (name "PDI") (class "Default")
      (node (ref "IC4") (pin "34") (pinfunction "PDI_DATA_34") (pintype "bidirectional"))
      (node (ref "JP1") (pin "1") (pinfunction "1_1") (pintype "passive"))
    )
    (net (code "176") (name "PE0") (class "Default")
      (node (ref "IC11") (pin "16") (pinfunction "B5_16") (pintype "bidirectional"))
      (node (ref "IC4") (pin "28") (pinfunction "PE0_28") (pintype "bidirectional"))
    )
    (net (code "177") (name "PE1") (class "Default")
      (node (ref "IC11") (pin "15") (pinfunction "B6_15") (pintype "bidirectional"))
      (node (ref "IC4") (pin "29") (pinfunction "PE1_29") (pintype "bidirectional"))
    )
    (net (code "178") (name "PE2") (class "Default")
      (node (ref "IC11") (pin "14") (pinfunction "B7_14") (pintype "bidirectional"))
      (node (ref "IC4") (pin "32") (pinfunction "PE2_32") (pintype "bidirectional"))
    )
    (net (code "179") (name "PE3") (class "Default")
      (node (ref "IC4") (pin "33") (pinfunction "PE3_33") (pintype "bidirectional"))
      (node (ref "R12") (pin "2") (pinfunction "P$2_2") (pintype "bidirectional"))
    )
    (net (code "180") (name "REACHED0") (class "Default")
      (node (ref "IC11") (pin "3") (pinfunction "A0_3") (pintype "bidirectional"))
      (node (ref "J12") (pin "2") (pinfunction "2_2") (pintype "bidirectional"))
    )
    (net (code "181") (name "REACHED1") (class "Default")
      (node (ref "IC11") (pin "4") (pinfunction "A1_4") (pintype "bidirectional"))
      (node (ref "J10") (pin "2") (pinfunction "2_2") (pintype "bidirectional"))
    )
    (net (code "182") (name "REACHED2") (class "Default")
      (node (ref "IC11") (pin "5") (pinfunction "A2_5") (pintype "bidirectional"))
      (node (ref "J7") (pin "2") (pinfunction "2_2") (pintype "bidirectional"))
    )
    (net (code "183") (name "RESET") (class "Default")
      (node (ref "IC4") (pin "35") (pinfunction "~{RESET}/PDI_CLK_35") (pintype "bidirectional"))
      (node (ref "JP1") (pin "5") (pinfunction "5_5") (pintype "passive"))
      (node (ref "R8") (pin "2") (pinfunction "P$2_2") (pintype "bidirectional"))
    )
    (net (code "184") (name "SCL0") (class "Default")
      (node (ref "R6") (pin "2") (pinfunction "P$2_2") (pintype "bidirectional"))
      (node (ref "U2") (pin "5") (pinfunction "TY(SCL)_5") (pintype "bidirectional"))
      (node (ref "U2") (pin "6") (pinfunction "RY(SCL)_6") (pintype "bidirectional"))
      (node (ref "U3") (pin "1") (pinfunction "SCL_1") (pintype "bidirectional"))
      (node (ref "U4") (pin "1") (pinfunction "SCL_1") (pintype "bidirectional"))
      (node (ref "U5") (pin "1") (pinfunction "SCL_1") (pintype "bidirectional"))
      (node (ref "U6") (pin "1") (pinfunction "SCL_1") (pintype "bidirectional"))
      (node (ref "U7") (pin "1") (pinfunction "SCL_1") (pintype "bidirectional"))
      (node (ref "U8") (pin "1") (pinfunction "SCL_1") (pintype "bidirectional"))
    )
    (net (code "185") (name "SDA0") (class "Default")
      (node (ref "R5") (pin "2") (pinfunction "P$2_2") (pintype "bidirectional"))
      (node (ref "U2") (pin "2") (pinfunction "RX(SDA)_2") (pintype "bidirectional"))
      (node (ref "U2") (pin "3") (pinfunction "TX(SDA)_3") (pintype "bidirectional"))
      (node (ref "U3") (pin "2") (pinfunction "SDA_2") (pintype "bidirectional"))
      (node (ref "U4") (pin "2") (pinfunction "SDA_2") (pintype "bidirectional"))
      (node (ref "U5") (pin "2") (pinfunction "SDA_2") (pintype "bidirectional"))
      (node (ref "U6") (pin "2") (pinfunction "SDA_2") (pintype "bidirectional"))
      (node (ref "U7") (pin "2") (pinfunction "SDA_2") (pintype "bidirectional"))
      (node (ref "U8") (pin "2") (pinfunction "SDA_2") (pintype "bidirectional"))
    )
    (net (code "186") (name "STEP0") (class "Default")
      (node (ref "IC7") (pin "3") (pinfunction "A0_3") (pintype "bidirectional"))
      (node (ref "J12") (pin "1") (pinfunction "1_1") (pintype "bidirectional"))
    )
    (net (code "187") (name "STEP1") (class "Default")
      (node (ref "IC7") (pin "4") (pinfunction "A1_4") (pintype "bidirectional"))
      (node (ref "J10") (pin "1") (pinfunction "1_1") (pintype "bidirectional"))
    )
    (net (code "188") (name "STEP2") (class "Default")
      (node (ref "IC7") (pin "7") (pinfunction "A4_7") (pintype "bidirectional"))
      (node (ref "J7") (pin "1") (pinfunction "1_1") (pintype "bidirectional"))
    )
    (net (code "189") (name "TODET0") (class "Default")
      (node (ref "IC5") (pin "7") (pinfunction "A4_7") (pintype "bidirectional"))
      (node (ref "J9") (pin "P$4") (pinfunction "4_P$4") (pintype "bidirectional"))
    )
    (net (code "190") (name "TODET1") (class "Default")
      (node (ref "IC5") (pin "8") (pinfunction "A5_8") (pintype "bidirectional"))
      (node (ref "J9") (pin "P$3") (pinfunction "3_P$3") (pintype "bidirectional"))
    )
    (net (code "191") (name "TODET2") (class "Default")
      (node (ref "IC5") (pin "9") (pinfunction "A6_9") (pintype "bidirectional"))
      (node (ref "J9") (pin "P$2") (pinfunction "2_P$2") (pintype "bidirectional"))
    )
    (net (code "192") (name "TODET3") (class "Default")
      (node (ref "IC5") (pin "10") (pinfunction "A7_10") (pintype "bidirectional"))
      (node (ref "J9") (pin "P$1") (pinfunction "1_P$1") (pintype "bidirectional"))
    )
    (net (code "193") (name "unconnected-(IC3A-R2OUT-Pad9)") (class "Default")
      (node (ref "IC3") (pin "9") (pinfunction "R2OUT_9") (pintype "output"))
    )
    (net (code "194") (name "unconnected-(IC3A-T2OUT-Pad7)") (class "Default")
      (node (ref "IC3") (pin "7") (pinfunction "T2OUT_7") (pintype "output"))
    )
    (net (code "195") (name "unconnected-(IC5-A3-Pad6)") (class "Default")
      (node (ref "IC5") (pin "6") (pinfunction "A3_6") (pintype "bidirectional"))
    )
    (net (code "196") (name "unconnected-(IC5-B3-Pad18)") (class "Default")
      (node (ref "IC5") (pin "18") (pinfunction "B3_18") (pintype "bidirectional"))
    )
    (net (code "197") (name "unconnected-(IC6-ACT0-Pad18)") (class "Default")
      (node (ref "IC6") (pin "18") (pinfunction "ACT0_18") (pintype "bidirectional"))
    )
    (net (code "198") (name "unconnected-(IC6-ACT1-Pad19)") (class "Default")
      (node (ref "IC6") (pin "19") (pinfunction "ACT1_19") (pintype "bidirectional"))
    )
    (net (code "199") (name "unconnected-(IC6-SLO-Pad1)") (class "Default")
      (node (ref "IC6") (pin "1") (pinfunction "SLO_1") (pintype "bidirectional"))
    )
    (net (code "200") (name "unconnected-(IC6-{slash}ERR-Pad11)") (class "Default")
      (node (ref "IC6") (pin "11") (pinfunction "/ERR_11") (pintype "bidirectional"))
    )
    (net (code "201") (name "unconnected-(IC6-{slash}WARN-Pad12)") (class "Default")
      (node (ref "IC6") (pin "12") (pinfunction "/WARN_12") (pintype "bidirectional"))
    )
    (net (code "202") (name "unconnected-(IC7-A2-Pad5)") (class "Default")
      (node (ref "IC7") (pin "5") (pinfunction "A2_5") (pintype "bidirectional"))
    )
    (net (code "203") (name "unconnected-(IC7-A3-Pad6)") (class "Default")
      (node (ref "IC7") (pin "6") (pinfunction "A3_6") (pintype "bidirectional"))
    )
    (net (code "204") (name "unconnected-(IC7-B2-Pad19)") (class "Default")
      (node (ref "IC7") (pin "19") (pinfunction "B2_19") (pintype "bidirectional"))
    )
    (net (code "205") (name "unconnected-(IC7-B3-Pad18)") (class "Default")
      (node (ref "IC7") (pin "18") (pinfunction "B3_18") (pintype "bidirectional"))
    )
    (net (code "206") (name "unconnected-(IC8-ACT0-Pad18)") (class "Default")
      (node (ref "IC8") (pin "18") (pinfunction "ACT0_18") (pintype "bidirectional"))
    )
    (net (code "207") (name "unconnected-(IC8-ACT1-Pad19)") (class "Default")
      (node (ref "IC8") (pin "19") (pinfunction "ACT1_19") (pintype "bidirectional"))
    )
    (net (code "208") (name "unconnected-(IC8-SLO-Pad1)") (class "Default")
      (node (ref "IC8") (pin "1") (pinfunction "SLO_1") (pintype "bidirectional"))
    )
    (net (code "209") (name "unconnected-(IC8-{slash}ERR-Pad11)") (class "Default")
      (node (ref "IC8") (pin "11") (pinfunction "/ERR_11") (pintype "bidirectional"))
    )
    (net (code "210") (name "unconnected-(IC8-{slash}WARN-Pad12)") (class "Default")
      (node (ref "IC8") (pin "12") (pinfunction "/WARN_12") (pintype "bidirectional"))
    )
    (net (code "211") (name "unconnected-(IC9-A4-Pad7)") (class "Default")
      (node (ref "IC9") (pin "7") (pinfunction "A4_7") (pintype "bidirectional"))
    )
    (net (code "212") (name "unconnected-(IC9-A5-Pad8)") (class "Default")
      (node (ref "IC9") (pin "8") (pinfunction "A5_8") (pintype "bidirectional"))
    )
    (net (code "213") (name "unconnected-(IC9-A6-Pad9)") (class "Default")
      (node (ref "IC9") (pin "9") (pinfunction "A6_9") (pintype "bidirectional"))
    )
    (net (code "214") (name "unconnected-(IC9-A7-Pad10)") (class "Default")
      (node (ref "IC9") (pin "10") (pinfunction "A7_10") (pintype "bidirectional"))
    )
    (net (code "215") (name "unconnected-(IC9-B4-Pad17)") (class "Default")
      (node (ref "IC9") (pin "17") (pinfunction "B4_17") (pintype "bidirectional"))
    )
    (net (code "216") (name "unconnected-(IC9-B5-Pad16)") (class "Default")
      (node (ref "IC9") (pin "16") (pinfunction "B5_16") (pintype "bidirectional"))
    )
    (net (code "217") (name "unconnected-(IC9-B6-Pad15)") (class "Default")
      (node (ref "IC9") (pin "15") (pinfunction "B6_15") (pintype "bidirectional"))
    )
    (net (code "218") (name "unconnected-(IC9-B7-Pad14)") (class "Default")
      (node (ref "IC9") (pin "14") (pinfunction "B7_14") (pintype "bidirectional"))
    )
    (net (code "219") (name "unconnected-(IC10-ACT0-Pad18)") (class "Default")
      (node (ref "IC10") (pin "18") (pinfunction "ACT0_18") (pintype "bidirectional"))
    )
    (net (code "220") (name "unconnected-(IC10-ACT1-Pad19)") (class "Default")
      (node (ref "IC10") (pin "19") (pinfunction "ACT1_19") (pintype "bidirectional"))
    )
    (net (code "221") (name "unconnected-(IC10-SLO-Pad1)") (class "Default")
      (node (ref "IC10") (pin "1") (pinfunction "SLO_1") (pintype "bidirectional"))
    )
    (net (code "222") (name "unconnected-(IC10-{slash}ERR-Pad11)") (class "Default")
      (node (ref "IC10") (pin "11") (pinfunction "/ERR_11") (pintype "bidirectional"))
    )
    (net (code "223") (name "unconnected-(IC10-{slash}WARN-Pad12)") (class "Default")
      (node (ref "IC10") (pin "12") (pinfunction "/WARN_12") (pintype "bidirectional"))
    )
    (net (code "224") (name "unconnected-(IC11-A3-Pad6)") (class "Default")
      (node (ref "IC11") (pin "6") (pinfunction "A3_6") (pintype "bidirectional"))
    )
    (net (code "225") (name "unconnected-(IC11-A4-Pad7)") (class "Default")
      (node (ref "IC11") (pin "7") (pinfunction "A4_7") (pintype "bidirectional"))
    )
    (net (code "226") (name "unconnected-(IC11-B3-Pad18)") (class "Default")
      (node (ref "IC11") (pin "18") (pinfunction "B3_18") (pintype "bidirectional"))
    )
    (net (code "227") (name "unconnected-(IC11-B4-Pad17)") (class "Default")
      (node (ref "IC11") (pin "17") (pinfunction "B4_17") (pintype "bidirectional"))
    )
    (net (code "228") (name "unconnected-(J2-1-PadP$1)") (class "Default")
      (node (ref "J2") (pin "P$1") (pinfunction "1_P$1") (pintype "bidirectional"))
    )
    (net (code "229") (name "unconnected-(J3-Pad1)") (class "Default")
      (node (ref "J3") (pin "1") (pinfunction "1_1") (pintype "bidirectional"))
    )
    (net (code "230") (name "unconnected-(J3-Pad2)") (class "Default")
      (node (ref "J3") (pin "2") (pinfunction "2_2") (pintype "bidirectional"))
    )
    (net (code "231") (name "unconnected-(J3-Pad4)") (class "Default")
      (node (ref "J3") (pin "4") (pinfunction "4_4") (pintype "bidirectional"))
    )
    (net (code "232") (name "unconnected-(J3-Pad6)") (class "Default")
      (node (ref "J3") (pin "6") (pinfunction "6_6") (pintype "bidirectional"))
    )
    (net (code "233") (name "unconnected-(J3-Pad7)") (class "Default")
      (node (ref "J3") (pin "7") (pinfunction "7_7") (pintype "bidirectional"))
    )
    (net (code "234") (name "unconnected-(J3-Pad8)") (class "Default")
      (node (ref "J3") (pin "8") (pinfunction "8_8") (pintype "bidirectional"))
    )
    (net (code "235") (name "unconnected-(J3-Pad10)") (class "Default")
      (node (ref "J3") (pin "10") (pinfunction "10_10") (pintype "bidirectional"))
    )
    (net (code "236") (name "unconnected-(J6-Pad1)") (class "Default")
      (node (ref "J6") (pin "1") (pinfunction "1_1") (pintype "bidirectional"))
    )
    (net (code "237") (name "unconnected-(J6-Pad2)") (class "Default")
      (node (ref "J6") (pin "2") (pinfunction "2_2") (pintype "bidirectional"))
    )
    (net (code "238") (name "unconnected-(J6-Pad4)") (class "Default")
      (node (ref "J6") (pin "4") (pinfunction "4_4") (pintype "bidirectional"))
    )
    (net (code "239") (name "unconnected-(J6-Pad6)") (class "Default")
      (node (ref "J6") (pin "6") (pinfunction "6_6") (pintype "bidirectional"))
    )
    (net (code "240") (name "unconnected-(J6-Pad7)") (class "Default")
      (node (ref "J6") (pin "7") (pinfunction "7_7") (pintype "bidirectional"))
    )
    (net (code "241") (name "unconnected-(J6-Pad8)") (class "Default")
      (node (ref "J6") (pin "8") (pinfunction "8_8") (pintype "bidirectional"))
    )
    (net (code "242") (name "unconnected-(J6-Pad10)") (class "Default")
      (node (ref "J6") (pin "10") (pinfunction "10_10") (pintype "bidirectional"))
    )
    (net (code "243") (name "unconnected-(J7-Pad4)") (class "Default")
      (node (ref "J7") (pin "4") (pinfunction "4_4") (pintype "bidirectional"))
    )
    (net (code "244") (name "unconnected-(J7-Pad17)") (class "Default")
      (node (ref "J7") (pin "17") (pinfunction "17_17") (pintype "bidirectional"))
    )
    (net (code "245") (name "unconnected-(J7-Pad19)") (class "Default")
      (node (ref "J7") (pin "19") (pinfunction "19_19") (pintype "bidirectional"))
    )
    (net (code "246") (name "unconnected-(J7-Pad23)") (class "Default")
      (node (ref "J7") (pin "23") (pinfunction "23_23") (pintype "bidirectional"))
    )
    (net (code "247") (name "unconnected-(J7-Pad25)") (class "Default")
      (node (ref "J7") (pin "25") (pinfunction "25_25") (pintype "bidirectional"))
    )
    (net (code "248") (name "unconnected-(J7-Pad26)") (class "Default")
      (node (ref "J7") (pin "26") (pinfunction "26_26") (pintype "bidirectional"))
    )
    (net (code "249") (name "unconnected-(J8-Pad1)") (class "Default")
      (node (ref "J8") (pin "1") (pinfunction "1_1") (pintype "bidirectional"))
    )
    (net (code "250") (name "unconnected-(J8-Pad2)") (class "Default")
      (node (ref "J8") (pin "2") (pinfunction "2_2") (pintype "bidirectional"))
    )
    (net (code "251") (name "unconnected-(J8-Pad4)") (class "Default")
      (node (ref "J8") (pin "4") (pinfunction "4_4") (pintype "bidirectional"))
    )
    (net (code "252") (name "unconnected-(J8-Pad6)") (class "Default")
      (node (ref "J8") (pin "6") (pinfunction "6_6") (pintype "bidirectional"))
    )
    (net (code "253") (name "unconnected-(J8-Pad7)") (class "Default")
      (node (ref "J8") (pin "7") (pinfunction "7_7") (pintype "bidirectional"))
    )
    (net (code "254") (name "unconnected-(J8-Pad8)") (class "Default")
      (node (ref "J8") (pin "8") (pinfunction "8_8") (pintype "bidirectional"))
    )
    (net (code "255") (name "unconnected-(J8-Pad10)") (class "Default")
      (node (ref "J8") (pin "10") (pinfunction "10_10") (pintype "bidirectional"))
    )
    (net (code "256") (name "unconnected-(J10-Pad4)") (class "Default")
      (node (ref "J10") (pin "4") (pinfunction "4_4") (pintype "bidirectional"))
    )
    (net (code "257") (name "unconnected-(J10-Pad17)") (class "Default")
      (node (ref "J10") (pin "17") (pinfunction "17_17") (pintype "bidirectional"))
    )
    (net (code "258") (name "unconnected-(J10-Pad19)") (class "Default")
      (node (ref "J10") (pin "19") (pinfunction "19_19") (pintype "bidirectional"))
    )
    (net (code "259") (name "unconnected-(J10-Pad23)") (class "Default")
      (node (ref "J10") (pin "23") (pinfunction "23_23") (pintype "bidirectional"))
    )
    (net (code "260") (name "unconnected-(J10-Pad25)") (class "Default")
      (node (ref "J10") (pin "25") (pinfunction "25_25") (pintype "bidirectional"))
    )
    (net (code "261") (name "unconnected-(J10-Pad26)") (class "Default")
      (node (ref "J10") (pin "26") (pinfunction "26_26") (pintype "bidirectional"))
    )
    (net (code "262") (name "unconnected-(J11-Pad1)") (class "Default")
      (node (ref "J11") (pin "1") (pinfunction "1_1") (pintype "bidirectional"))
    )
    (net (code "263") (name "unconnected-(J11-Pad2)") (class "Default")
      (node (ref "J11") (pin "2") (pinfunction "2_2") (pintype "bidirectional"))
    )
    (net (code "264") (name "unconnected-(J11-Pad4)") (class "Default")
      (node (ref "J11") (pin "4") (pinfunction "4_4") (pintype "bidirectional"))
    )
    (net (code "265") (name "unconnected-(J11-Pad6)") (class "Default")
      (node (ref "J11") (pin "6") (pinfunction "6_6") (pintype "bidirectional"))
    )
    (net (code "266") (name "unconnected-(J11-Pad7)") (class "Default")
      (node (ref "J11") (pin "7") (pinfunction "7_7") (pintype "bidirectional"))
    )
    (net (code "267") (name "unconnected-(J11-Pad8)") (class "Default")
      (node (ref "J11") (pin "8") (pinfunction "8_8") (pintype "bidirectional"))
    )
    (net (code "268") (name "unconnected-(J11-Pad10)") (class "Default")
      (node (ref "J11") (pin "10") (pinfunction "10_10") (pintype "bidirectional"))
    )
    (net (code "269") (name "unconnected-(J12-Pad4)") (class "Default")
      (node (ref "J12") (pin "4") (pinfunction "4_4") (pintype "bidirectional"))
    )
    (net (code "270") (name "unconnected-(J12-Pad17)") (class "Default")
      (node (ref "J12") (pin "17") (pinfunction "17_17") (pintype "bidirectional"))
    )
    (net (code "271") (name "unconnected-(J12-Pad19)") (class "Default")
      (node (ref "J12") (pin "19") (pinfunction "19_19") (pintype "bidirectional"))
    )
    (net (code "272") (name "unconnected-(J12-Pad23)") (class "Default")
      (node (ref "J12") (pin "23") (pinfunction "23_23") (pintype "bidirectional"))
    )
    (net (code "273") (name "unconnected-(J12-Pad25)") (class "Default")
      (node (ref "J12") (pin "25") (pinfunction "25_25") (pintype "bidirectional"))
    )
    (net (code "274") (name "unconnected-(J12-Pad26)") (class "Default")
      (node (ref "J12") (pin "26") (pinfunction "26_26") (pintype "bidirectional"))
    )
    (net (code "275") (name "unconnected-(JP1-Pad3)") (class "Default")
      (node (ref "JP1") (pin "3") (pinfunction "3_3") (pintype "passive"))
    )
    (net (code "276") (name "unconnected-(JP1-Pad4)") (class "Default")
      (node (ref "JP1") (pin "4") (pinfunction "4_4") (pintype "passive"))
    )
    (net (code "277") (name "unconnected-(R7-P$1-Pad1)") (class "Default")
      (node (ref "R7") (pin "1") (pinfunction "P$1_1") (pintype "bidirectional"))
    )
    (net (code "278") (name "unconnected-(U3-IO7-Pad14)") (class "Default")
      (node (ref "U3") (pin "14") (pinfunction "IO7_14") (pintype "bidirectional"))
    )
    (net (code "279") (name "unconnected-(U4-IO5-Pad12)") (class "Default")
      (node (ref "U4") (pin "12") (pinfunction "IO5_12") (pintype "bidirectional"))
    )
    (net (code "280") (name "unconnected-(U4-IO6-Pad13)") (class "Default")
      (node (ref "U4") (pin "13") (pinfunction "IO6_13") (pintype "bidirectional"))
    )
    (net (code "281") (name "unconnected-(U4-IO7-Pad14)") (class "Default")
      (node (ref "U4") (pin "14") (pinfunction "IO7_14") (pintype "bidirectional"))
    )
    (net (code "282") (name "unconnected-(U5-IO6-Pad13)") (class "Default")
      (node (ref "U5") (pin "13") (pinfunction "IO6_13") (pintype "bidirectional"))
    )
    (net (code "283") (name "unconnected-(U5-IO7-Pad14)") (class "Default")
      (node (ref "U5") (pin "14") (pinfunction "IO7_14") (pintype "bidirectional"))
    )
    (net (code "284") (name "unconnected-(U6-IO3-Pad10)") (class "Default")
      (node (ref "U6") (pin "10") (pinfunction "IO3_10") (pintype "bidirectional"))
    )
    (net (code "285") (name "unconnected-(U6-IO4-Pad11)") (class "Default")
      (node (ref "U6") (pin "11") (pinfunction "IO4_11") (pintype "bidirectional"))
    )
    (net (code "286") (name "unconnected-(U6-IO5-Pad12)") (class "Default")
      (node (ref "U6") (pin "12") (pinfunction "IO5_12") (pintype "bidirectional"))
    )
    (net (code "287") (name "unconnected-(U6-IO6-Pad13)") (class "Default")
      (node (ref "U6") (pin "13") (pinfunction "IO6_13") (pintype "bidirectional"))
    )
    (net (code "288") (name "unconnected-(U6-IO7-Pad14)") (class "Default")
      (node (ref "U6") (pin "14") (pinfunction "IO7_14") (pintype "bidirectional"))
    )
    (net (code "289") (name "unconnected-(U7-IO6-Pad13)") (class "Default")
      (node (ref "U7") (pin "13") (pinfunction "IO6_13") (pintype "bidirectional"))
    )
    (net (code "290") (name "unconnected-(U7-IO7-Pad14)") (class "Default")
      (node (ref "U7") (pin "14") (pinfunction "IO7_14") (pintype "bidirectional"))
    )
    (net (code "291") (name "unconnected-(U8-IO3-Pad10)") (class "Default")
      (node (ref "U8") (pin "10") (pinfunction "IO3_10") (pintype "bidirectional"))
    )
    (net (code "292") (name "unconnected-(U8-IO4-Pad11)") (class "Default")
      (node (ref "U8") (pin "11") (pinfunction "IO4_11") (pintype "bidirectional"))
    )
    (net (code "293") (name "unconnected-(U8-IO5-Pad12)") (class "Default")
      (node (ref "U8") (pin "12") (pinfunction "IO5_12") (pintype "bidirectional"))
    )
    (net (code "294") (name "unconnected-(U8-IO6-Pad13)") (class "Default")
      (node (ref "U8") (pin "13") (pinfunction "IO6_13") (pintype "bidirectional"))
    )
    (net (code "295") (name "unconnected-(U8-IO7-Pad14)") (class "Default")
      (node (ref "U8") (pin "14") (pinfunction "IO7_14") (pintype "bidirectional"))
    )
    (net (code "296") (name "{slash}SPICS0") (class "Default")
      (node (ref "IC10") (pin "16") (pinfunction "/CS_16") (pintype "bidirectional"))
      (node (ref "IC5") (pin "3") (pinfunction "A0_3") (pintype "bidirectional"))
    )
    (net (code "297") (name "{slash}SPICS1") (class "Default")
      (node (ref "IC5") (pin "4") (pinfunction "A1_4") (pintype "bidirectional"))
      (node (ref "IC8") (pin "16") (pinfunction "/CS_16") (pintype "bidirectional"))
    )
    (net (code "298") (name "{slash}SPICS2") (class "Default")
      (node (ref "IC5") (pin "5") (pinfunction "A2_5") (pintype "bidirectional"))
      (node (ref "IC6") (pin "16") (pinfunction "/CS_16") (pintype "bidirectional"))
    )
  )
)
